# PM_Controller_v1p00.net
KiCad netlist of a schematic drawn in EAGLE
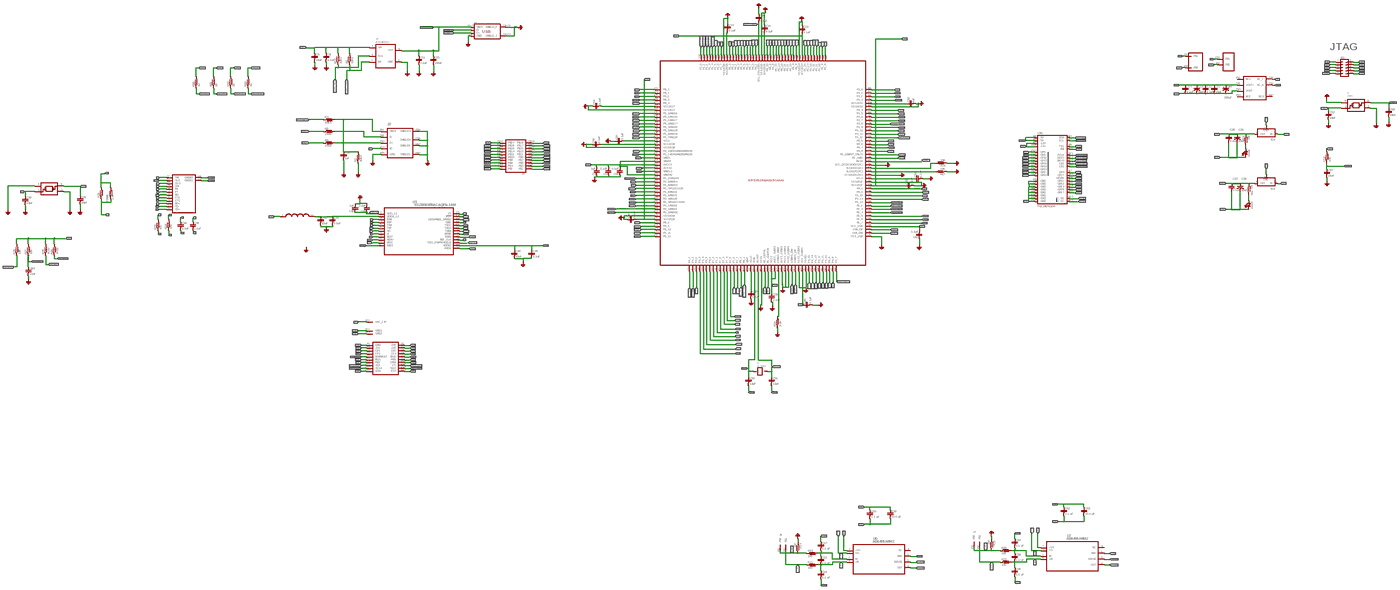
[diagram p0: schematic, sheet 1, overview]
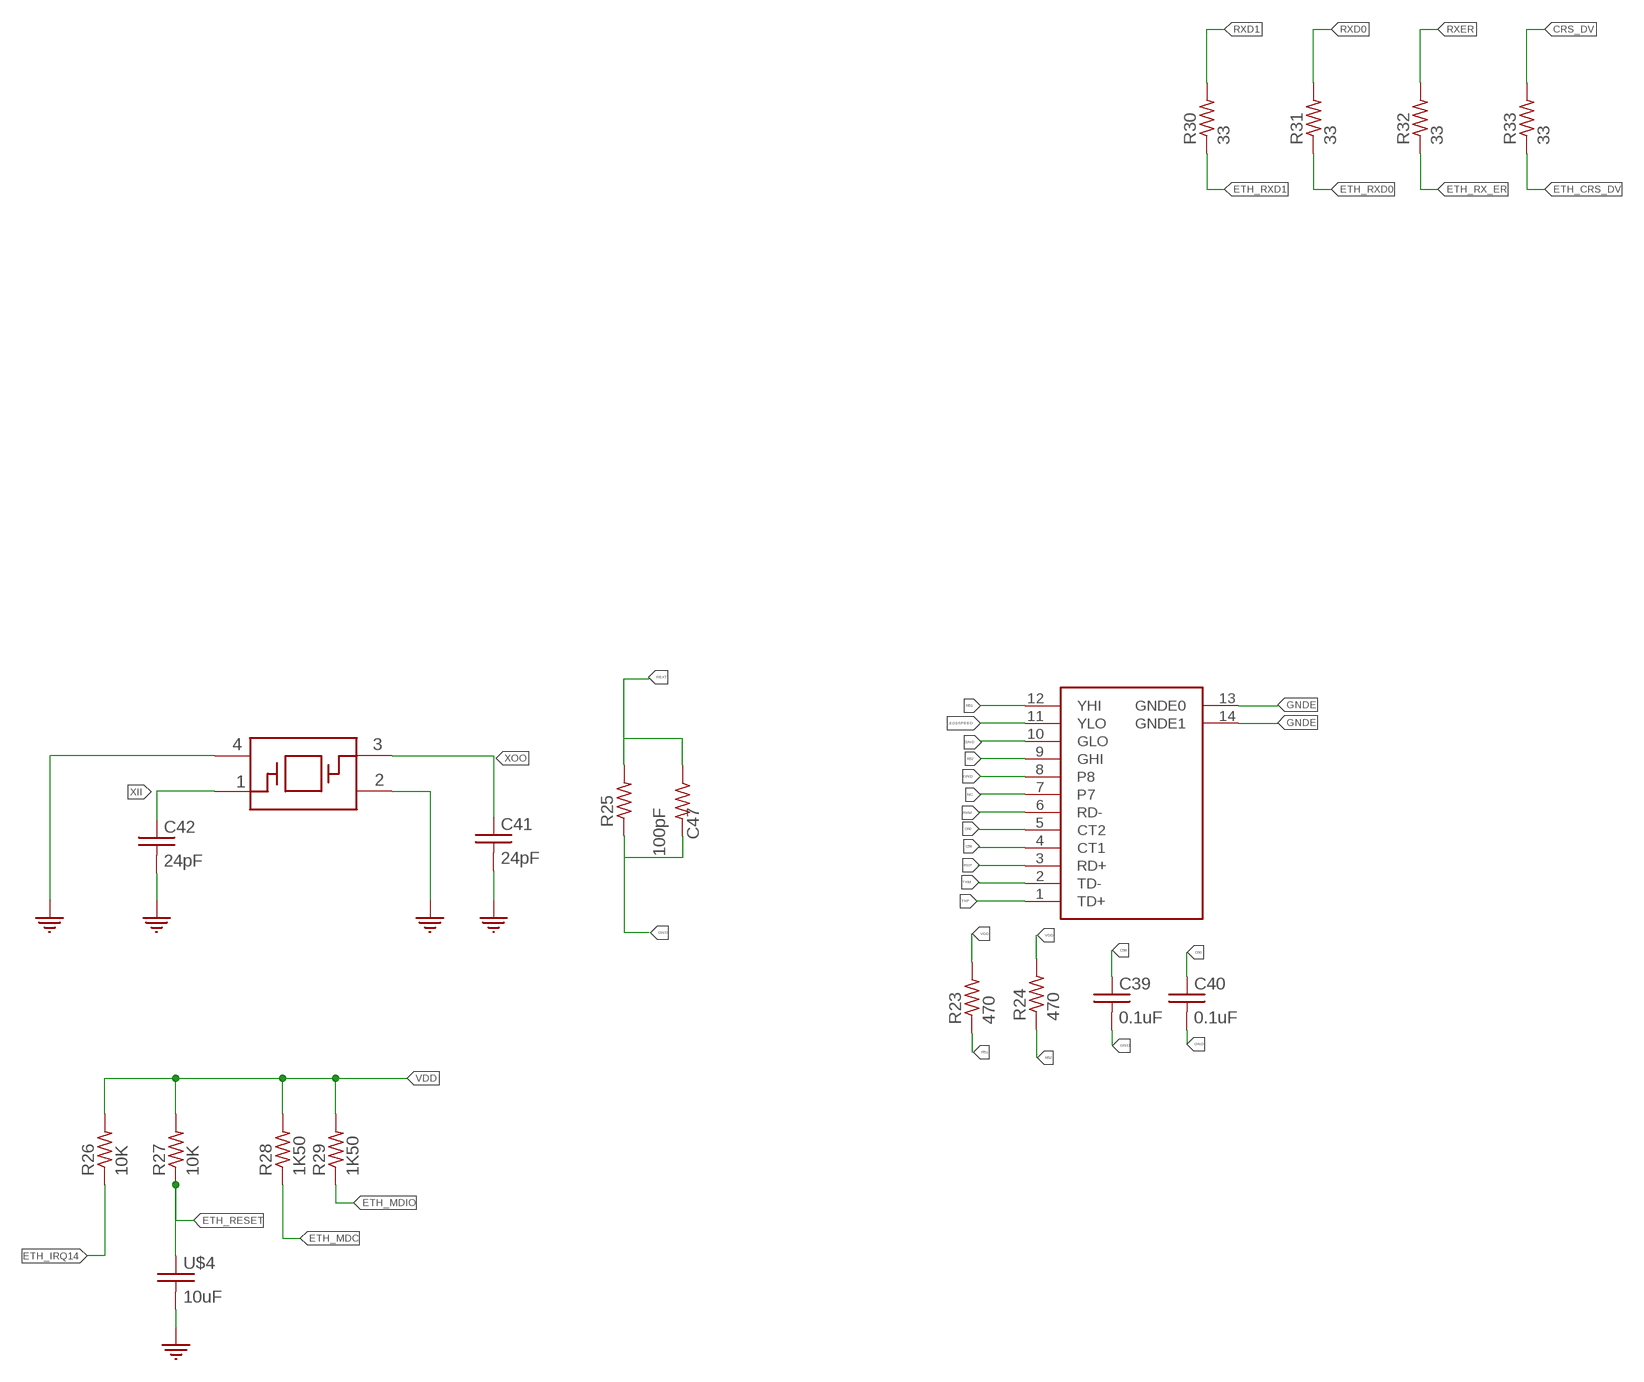
[diagram p1: schematic, sheet 1, part 1 of 6]
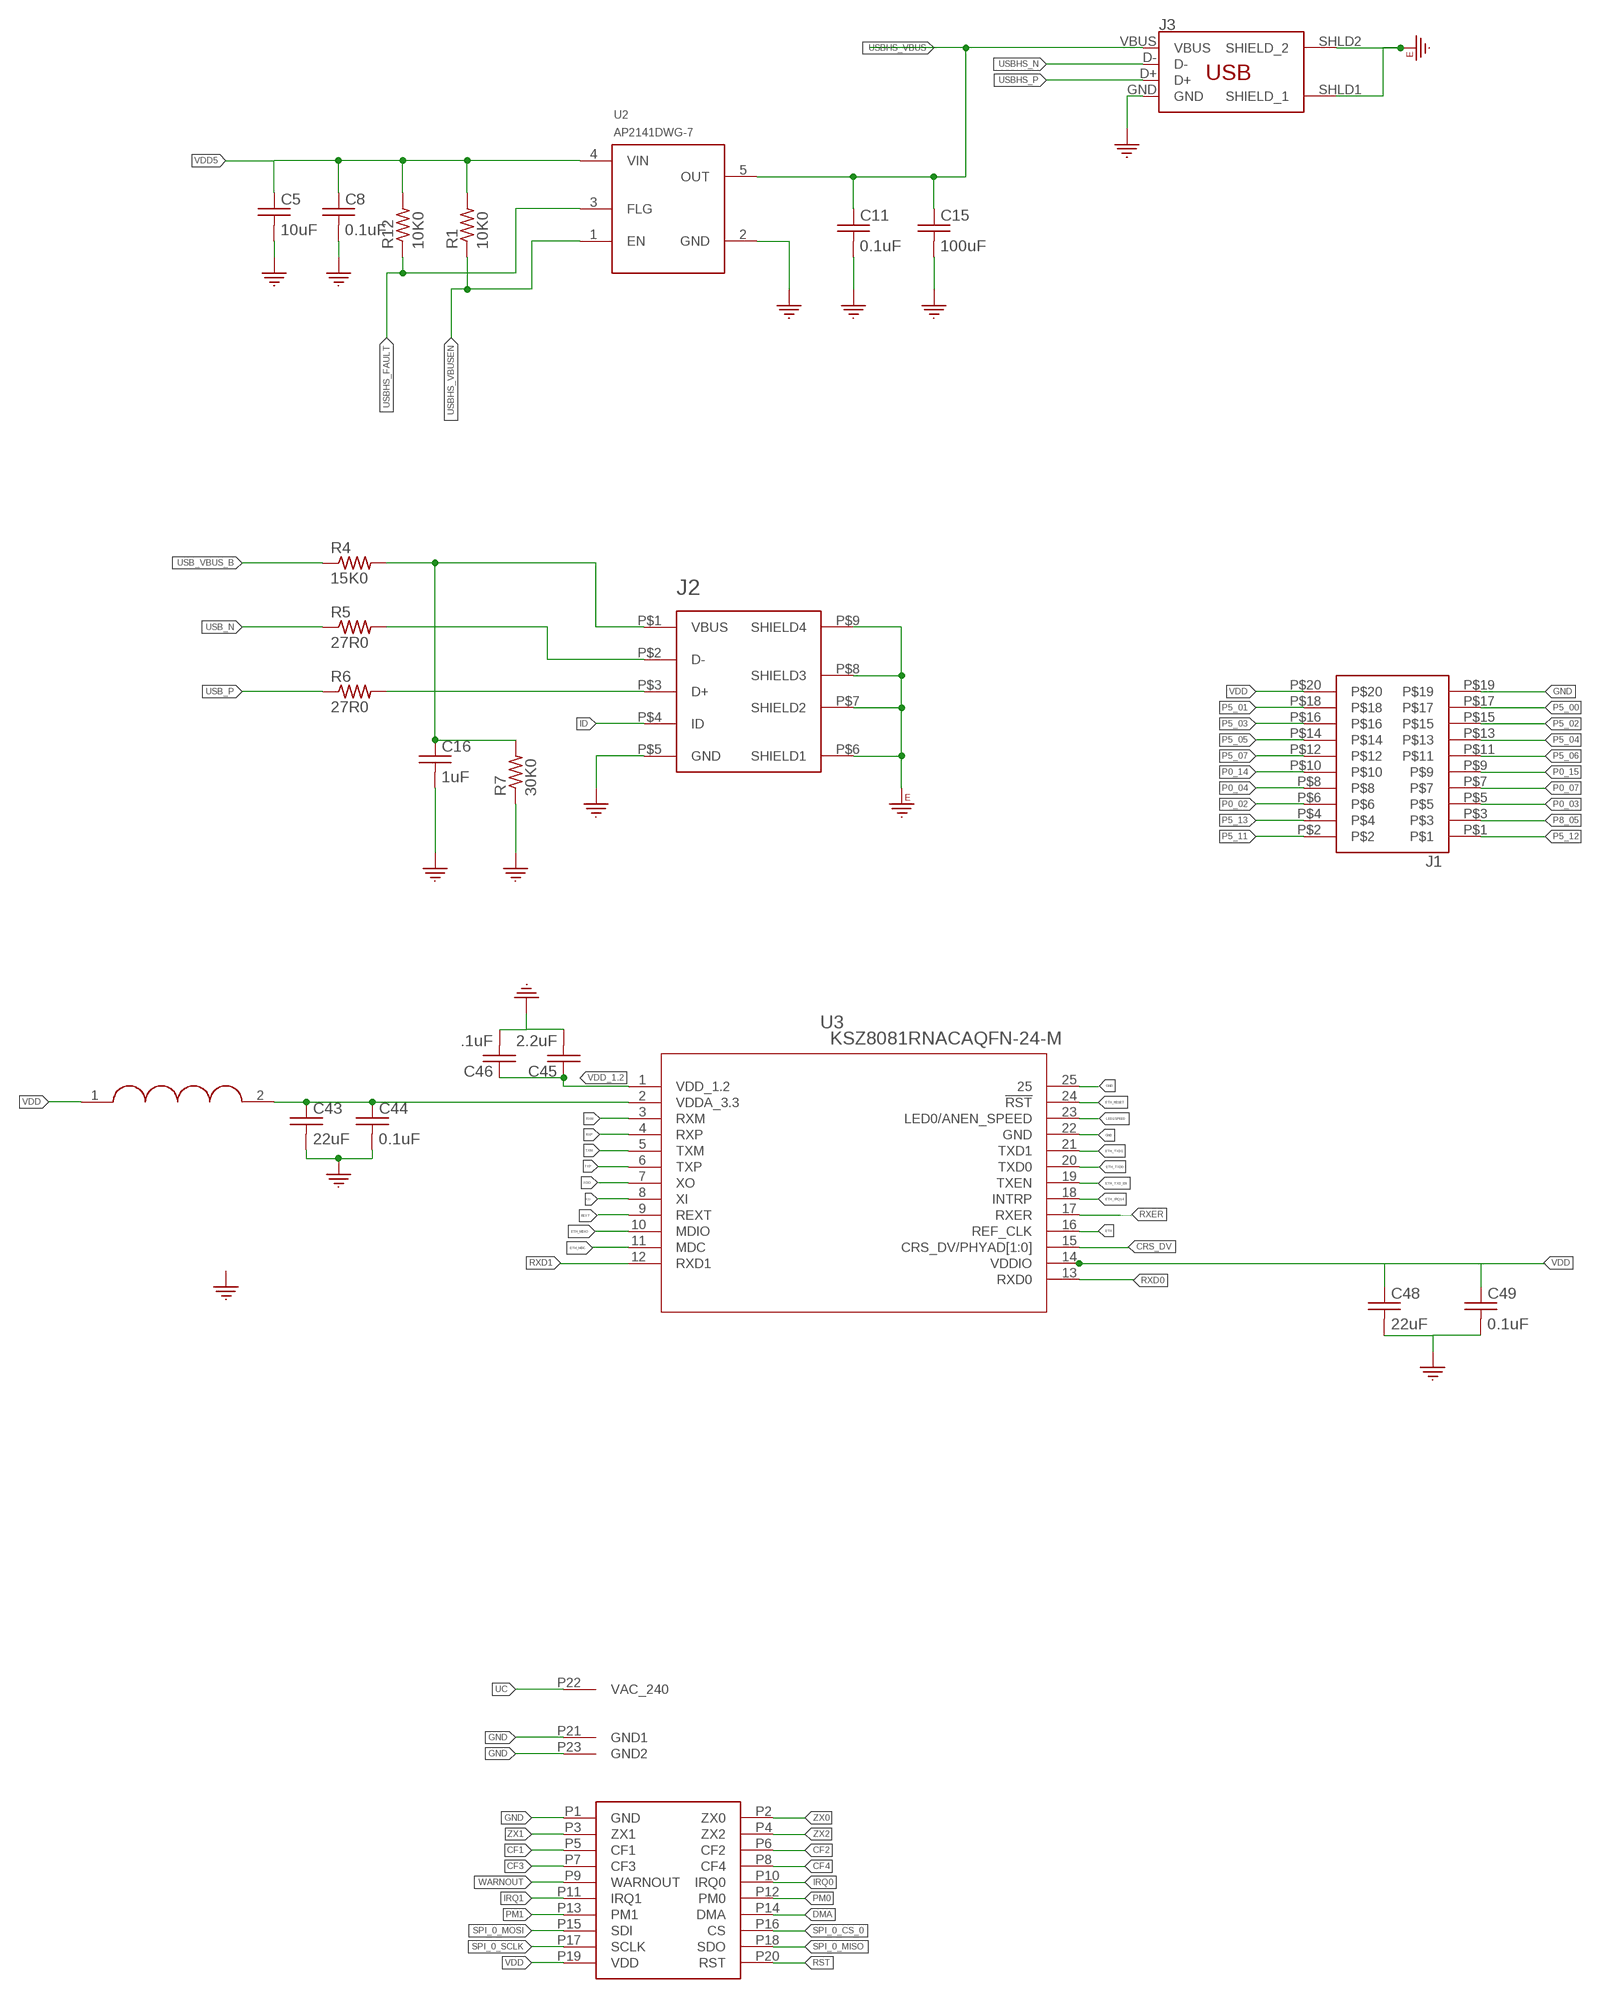
[diagram p2: schematic, sheet 1, part 2 of 6]
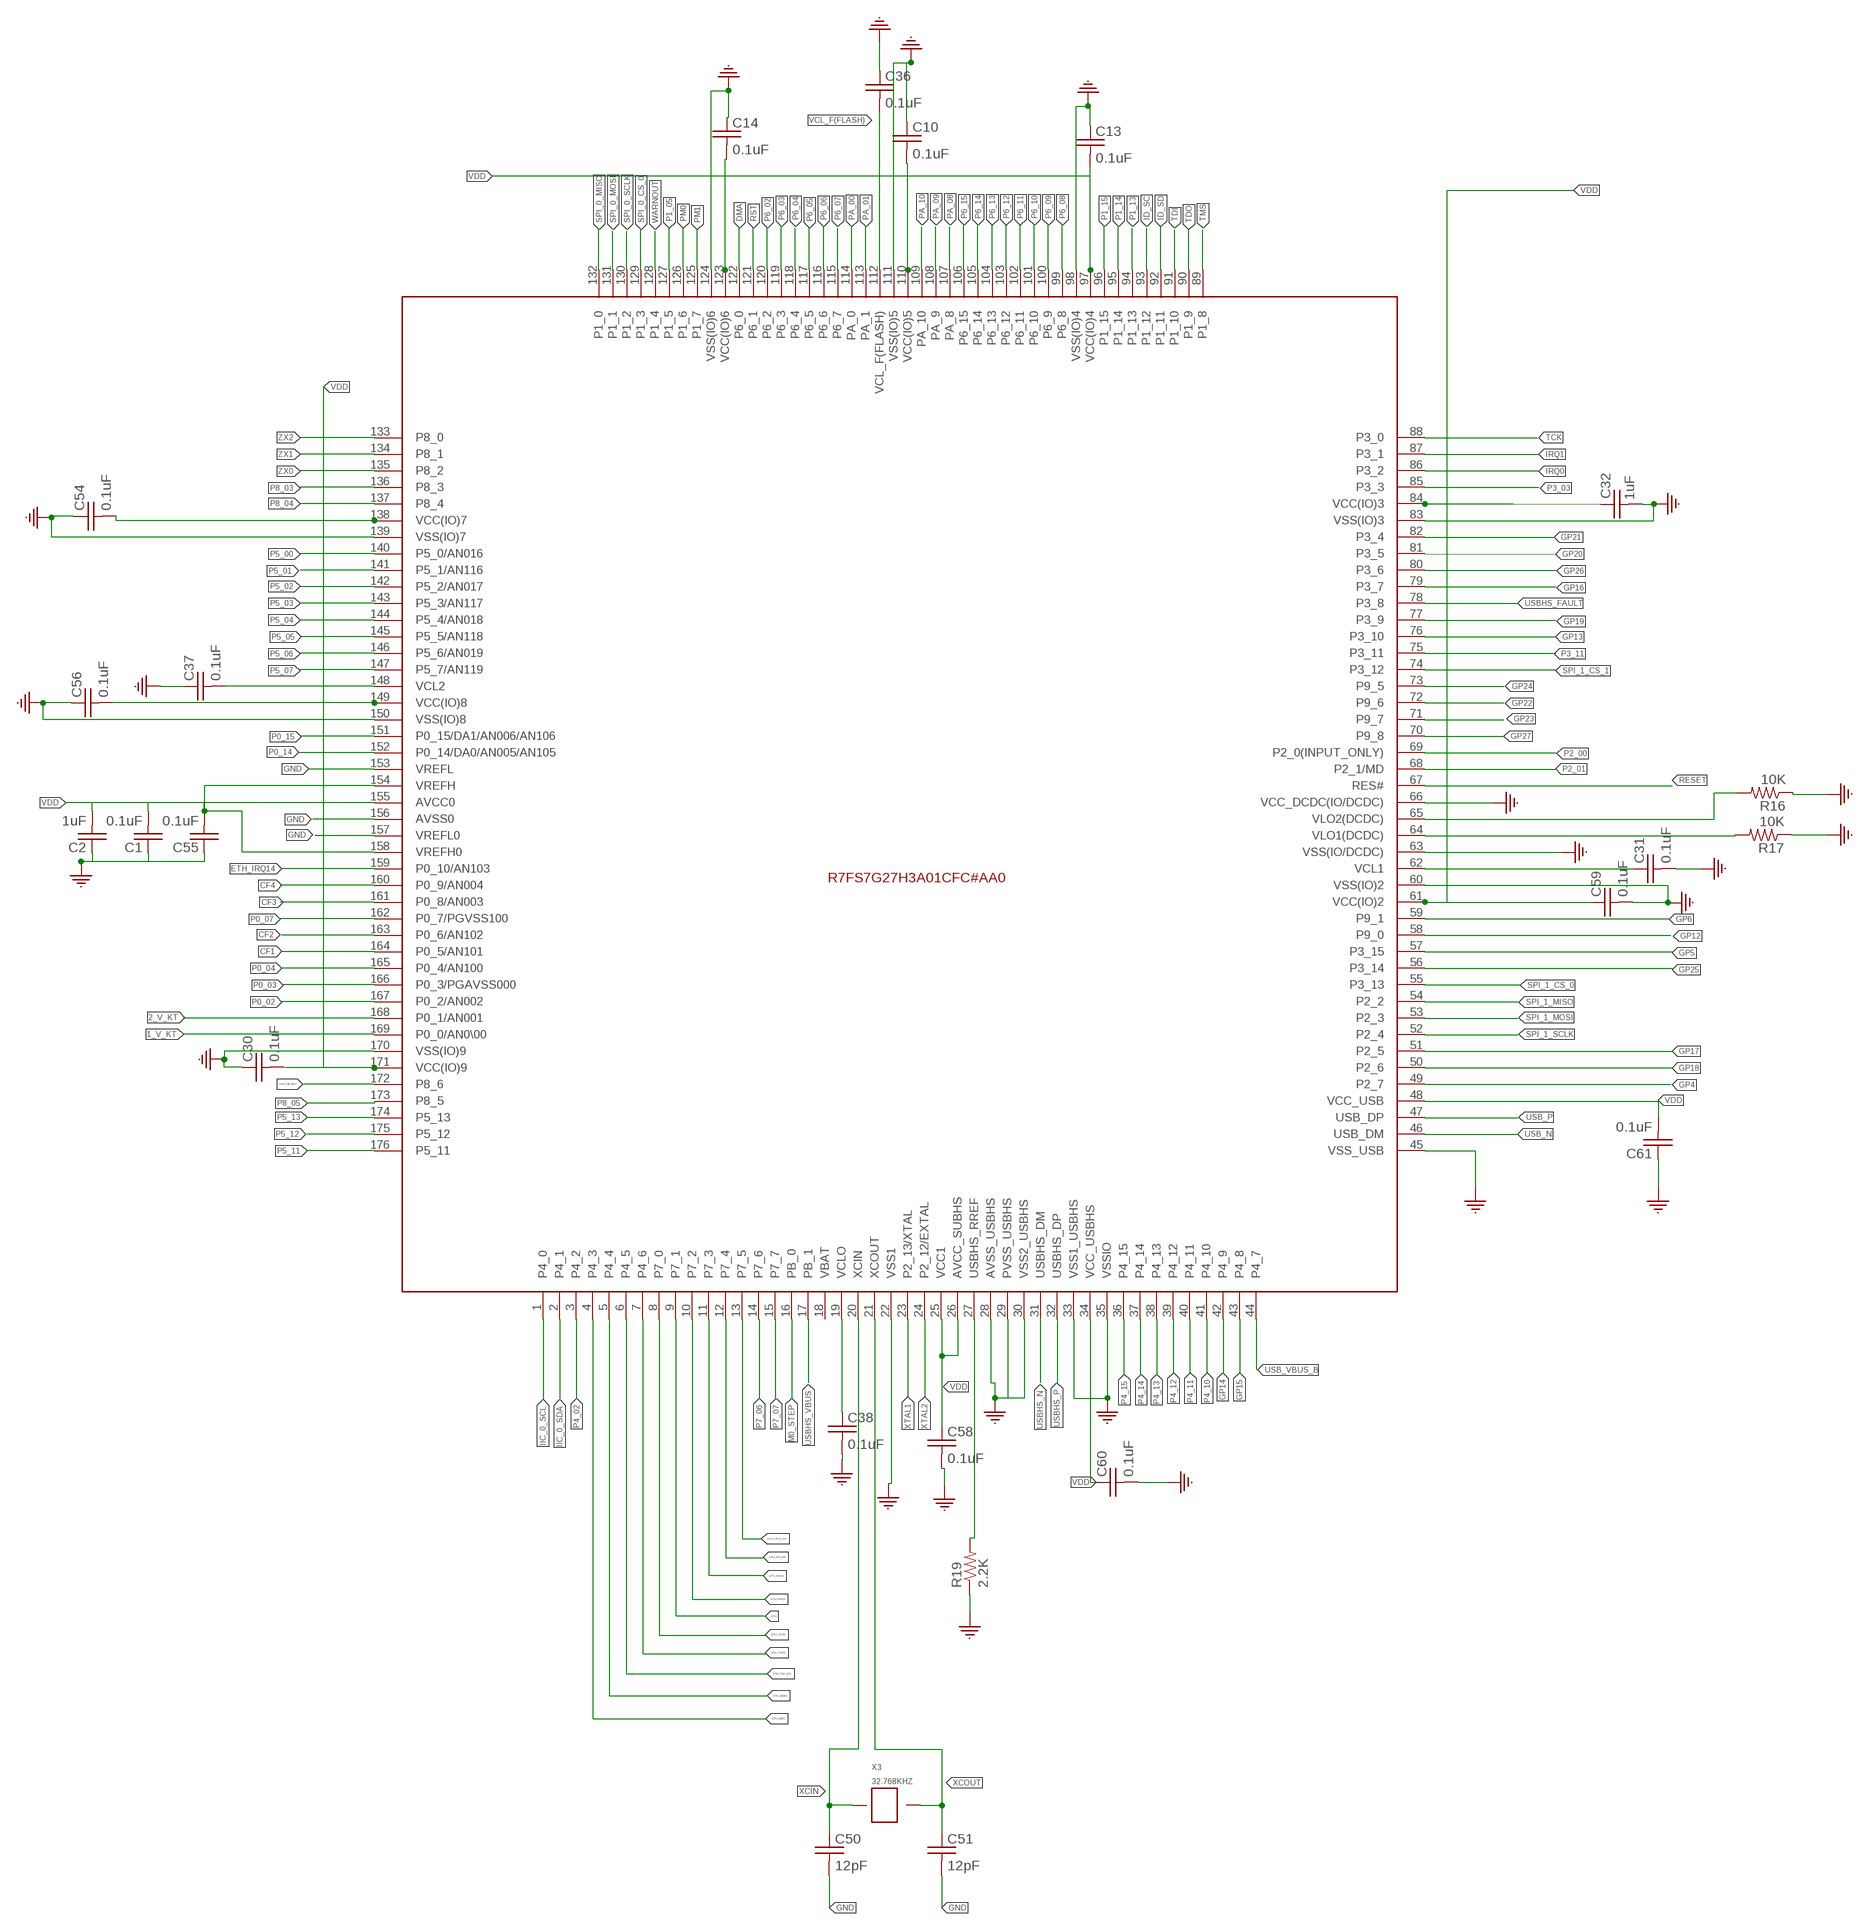
[diagram p3: schematic, sheet 1, part 3 of 6]
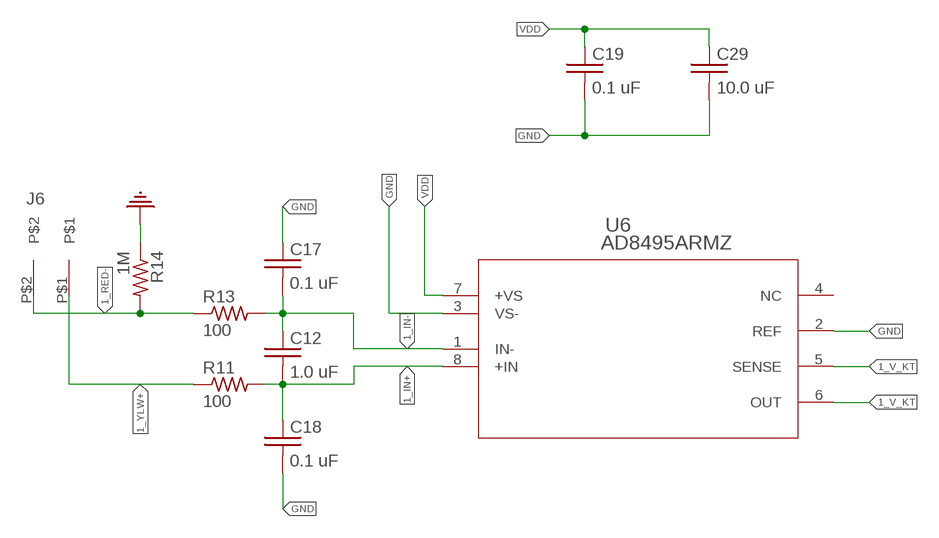
[diagram p4: schematic, sheet 1, part 4 of 6]
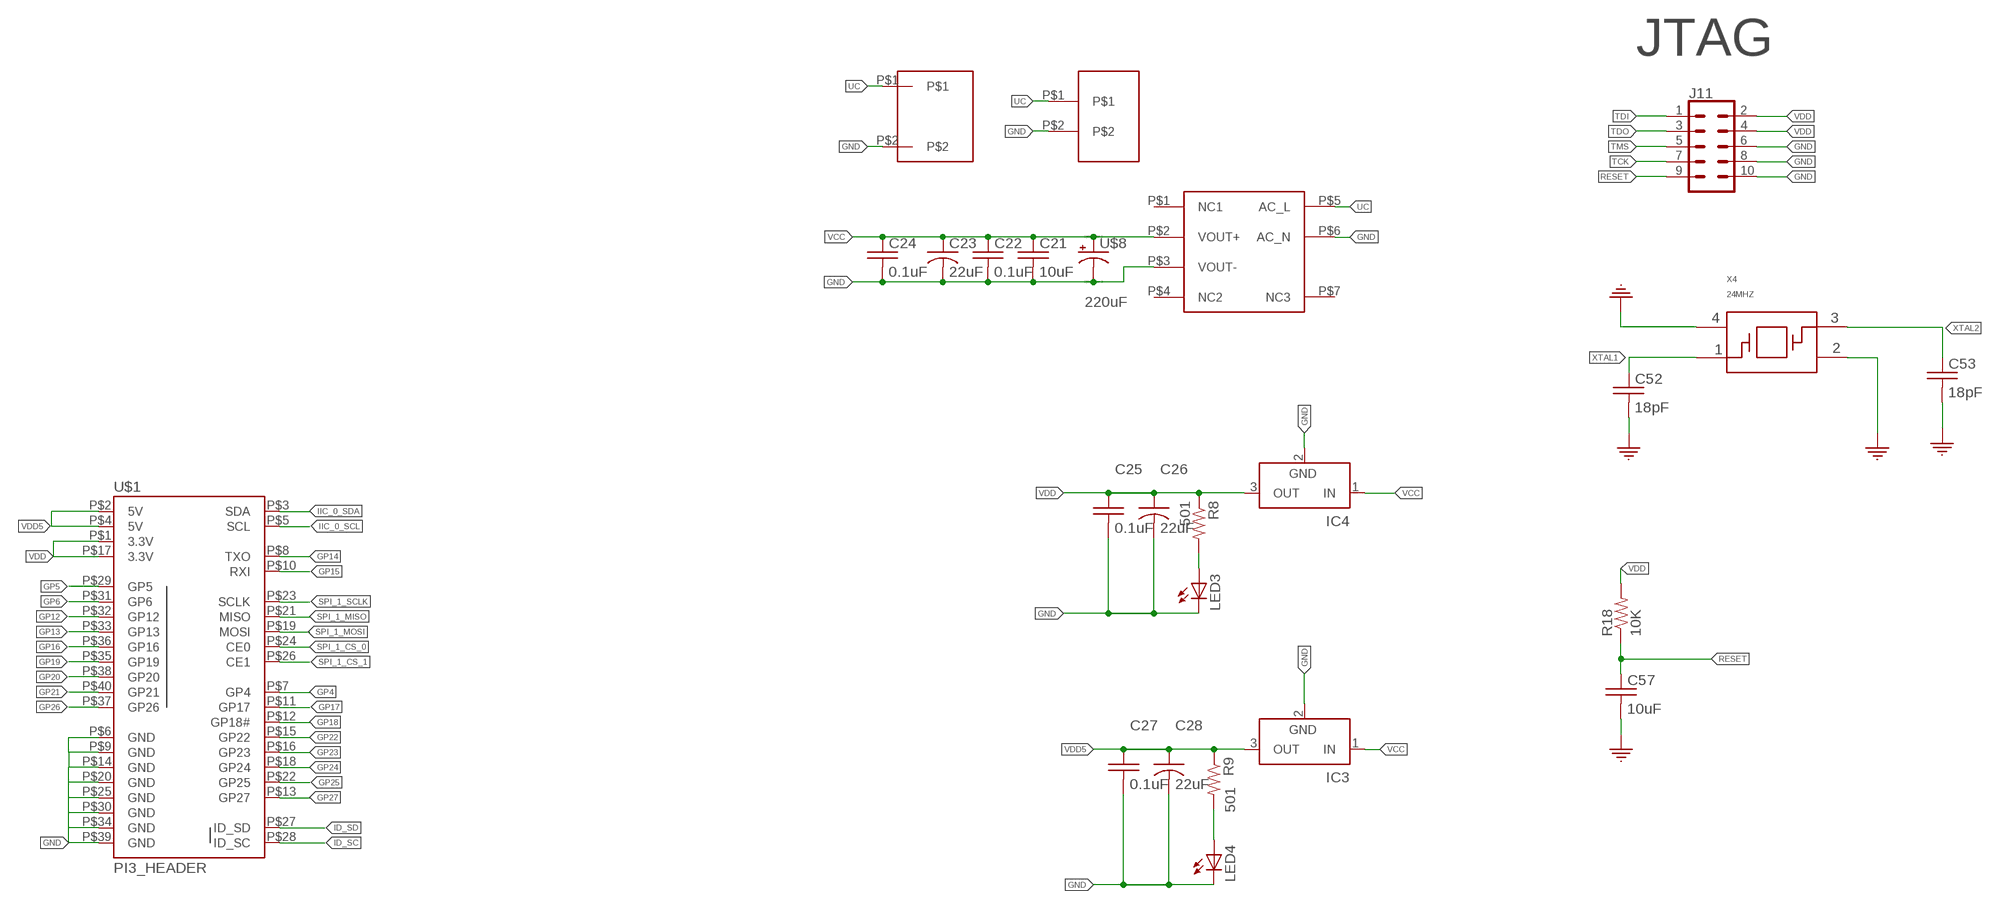
[diagram p5: schematic, sheet 1, part 5 of 6]
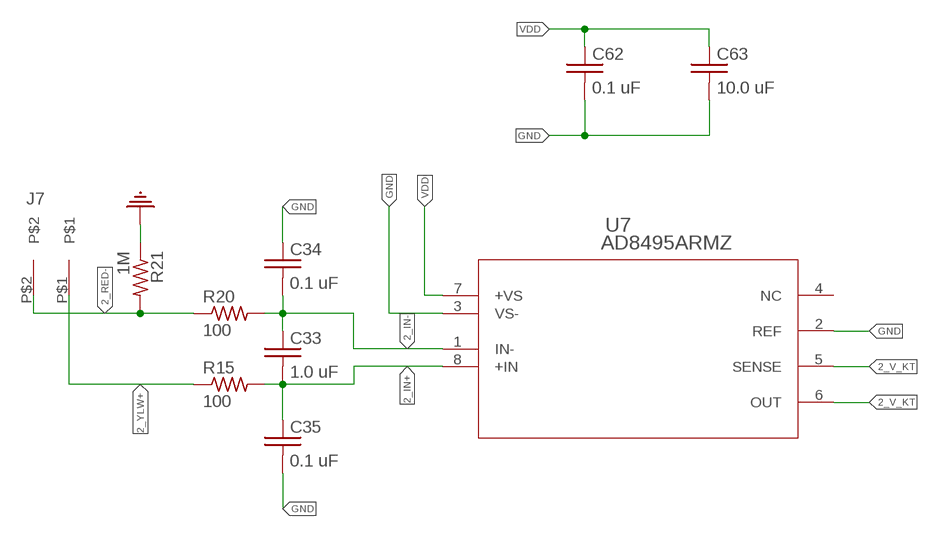
[diagram p6: schematic, sheet 1, part 6 of 6]

(export (version "E")
  (design (tool "Eeschema 10.0.6"))
  (components
    (comp (ref "C1")
      (value "0.1uF")
      (footprint "eagle-import:0402")
      (libsource (lib "eagle-import") (part "C_0402"))
    )
    (comp (ref "C2")
      (value "1uF")
      (footprint "eagle-import:0402")
      (libsource (lib "eagle-import") (part "C_0402"))
    )
    (comp (ref "C5")
      (value "10uF")
      (footprint "eagle-import:0402")
      (libsource (lib "eagle-import") (part "C_0402"))
    )
    (comp (ref "C8")
      (value "0.1uF")
      (footprint "eagle-import:0402")
      (libsource (lib "eagle-import") (part "C_0402"))
    )
    (comp (ref "C10")
      (value "0.1uF")
      (footprint "eagle-import:0402")
      (libsource (lib "eagle-import") (part "C_0402"))
    )
    (comp (ref "C11")
      (value "0.1uF")
      (footprint "eagle-import:0402")
      (libsource (lib "eagle-import") (part "C_0402"))
    )
    (comp (ref "C12")
      (value "1.0 uF")
      (footprint "eagle-import:0402")
      (libsource (lib "eagle-import") (part "C_0402"))
    )
    (comp (ref "C13")
      (value "0.1uF")
      (footprint "eagle-import:0402")
      (libsource (lib "eagle-import") (part "C_0402"))
    )
    (comp (ref "C14")
      (value "0.1uF")
      (footprint "eagle-import:0402")
      (libsource (lib "eagle-import") (part "C_0402"))
    )
    (comp (ref "C15")
      (value "100uF")
      (footprint "eagle-import:C1210")
      (libsource (lib "eagle-import") (part "C_1210"))
    )
    (comp (ref "C16")
      (value "1uF")
      (footprint "eagle-import:0402")
      (libsource (lib "eagle-import") (part "C_0402"))
    )
    (comp (ref "C17")
      (value "0.1 uF")
      (footprint "eagle-import:0402")
      (libsource (lib "eagle-import") (part "C_0402"))
    )
    (comp (ref "C18")
      (value "0.1 uF")
      (footprint "eagle-import:0402")
      (libsource (lib "eagle-import") (part "C_0402"))
    )
    (comp (ref "C19")
      (value "0.1 uF")
      (footprint "eagle-import:0402")
      (libsource (lib "eagle-import") (part "C_0402"))
    )
    (comp (ref "C20")
      (value "CAP_THIN_FILM_TDK_32922CAP")
      (footprint "eagle-import:CAP_THIN_FILM_32922")
      (libsource (lib "eagle-import") (part "CAP_THIN_FILM_TDK_32922CAP"))
    )
    (comp (ref "C21")
      (value "10uF")
      (footprint "eagle-import:0402")
      (libsource (lib "eagle-import") (part "C_0402"))
    )
    (comp (ref "C22")
      (value "0.1uF")
      (footprint "eagle-import:0402")
      (libsource (lib "eagle-import") (part "C_0402"))
    )
    (comp (ref "C23")
      (value "22uF")
      (footprint "eagle-import:C1206")
      (libsource (lib "eagle-import") (part "C-USC1206"))
    )
    (comp (ref "C24")
      (value "0.1uF")
      (footprint "eagle-import:0402")
      (libsource (lib "eagle-import") (part "C_0402"))
    )
    (comp (ref "C25")
      (value "0.1uF")
      (footprint "eagle-import:0402")
      (libsource (lib "eagle-import") (part "C_0402"))
    )
    (comp (ref "C26")
      (value "22uF")
      (footprint "eagle-import:C1206")
      (libsource (lib "eagle-import") (part "C-USC1206"))
    )
    (comp (ref "C27")
      (value "0.1uF")
      (footprint "eagle-import:0402")
      (libsource (lib "eagle-import") (part "C_0402"))
    )
    (comp (ref "C28")
      (value "22uF")
      (footprint "eagle-import:C1206")
      (libsource (lib "eagle-import") (part "C-USC1206"))
    )
    (comp (ref "C29")
      (value "10.0 uF")
      (footprint "eagle-import:0402")
      (libsource (lib "eagle-import") (part "C_0402"))
    )
    (comp (ref "C30")
      (value "0.1uF")
      (footprint "eagle-import:0402")
      (libsource (lib "eagle-import") (part "C_0402"))
    )
    (comp (ref "C31")
      (value "0.1uF")
      (footprint "eagle-import:0402")
      (libsource (lib "eagle-import") (part "C_0402"))
    )
    (comp (ref "C32")
      (value "1uF")
      (footprint "eagle-import:0402")
      (libsource (lib "eagle-import") (part "C_0402"))
    )
    (comp (ref "C33")
      (value "1.0 uF")
      (footprint "eagle-import:0402")
      (libsource (lib "eagle-import") (part "C_0402"))
    )
    (comp (ref "C34")
      (value "0.1 uF")
      (footprint "eagle-import:0402")
      (libsource (lib "eagle-import") (part "C_0402"))
    )
    (comp (ref "C35")
      (value "0.1 uF")
      (footprint "eagle-import:0402")
      (libsource (lib "eagle-import") (part "C_0402"))
    )
    (comp (ref "C36")
      (value "0.1uF")
      (footprint "eagle-import:0402")
      (libsource (lib "eagle-import") (part "C_0402"))
    )
    (comp (ref "C37")
      (value "0.1uF")
      (footprint "eagle-import:0402")
      (libsource (lib "eagle-import") (part "C_0402"))
    )
    (comp (ref "C38")
      (value "0.1uF")
      (footprint "eagle-import:0402")
      (libsource (lib "eagle-import") (part "C_0402"))
    )
    (comp (ref "C39")
      (value "0.1uF")
      (footprint "eagle-import:0402")
      (libsource (lib "eagle-import") (part "C_0402"))
    )
    (comp (ref "C40")
      (value "0.1uF")
      (footprint "eagle-import:0402")
      (libsource (lib "eagle-import") (part "C_0402"))
    )
    (comp (ref "C41")
      (value "24pF")
      (footprint "eagle-import:0402")
      (libsource (lib "eagle-import") (part "C_0402"))
    )
    (comp (ref "C42")
      (value "24pF")
      (footprint "eagle-import:0402")
      (libsource (lib "eagle-import") (part "C_0402"))
    )
    (comp (ref "C43")
      (value "22uF")
      (footprint "eagle-import:0603")
      (libsource (lib "eagle-import") (part "C_0603"))
    )
    (comp (ref "C44")
      (value "0.1uF")
      (footprint "eagle-import:0402")
      (libsource (lib "eagle-import") (part "C_0402"))
    )
    (comp (ref "C45")
      (value "2.2uF")
      (footprint "eagle-import:0402")
      (libsource (lib "eagle-import") (part "C_0402"))
    )
    (comp (ref "C46")
      (value ".1uF")
      (footprint "eagle-import:0402")
      (libsource (lib "eagle-import") (part "C_0402"))
    )
    (comp (ref "C47")
      (value "100pF")
      (footprint "eagle-import:0402")
      (libsource (lib "eagle-import") (part "R_0402"))
    )
    (comp (ref "C48")
      (value "22uF")
      (footprint "eagle-import:0603")
      (libsource (lib "eagle-import") (part "C_0603"))
    )
    (comp (ref "C49")
      (value "0.1uF")
      (footprint "eagle-import:0402")
      (libsource (lib "eagle-import") (part "C_0402"))
    )
    (comp (ref "C50")
      (value "12pF")
      (footprint "eagle-import:0402")
      (libsource (lib "eagle-import") (part "C_0402"))
    )
    (comp (ref "C51")
      (value "12pF")
      (footprint "eagle-import:0402")
      (libsource (lib "eagle-import") (part "C_0402"))
    )
    (comp (ref "C52")
      (value "18pF")
      (footprint "eagle-import:0402")
      (libsource (lib "eagle-import") (part "C_0402"))
    )
    (comp (ref "C53")
      (value "18pF")
      (footprint "eagle-import:0402")
      (libsource (lib "eagle-import") (part "C_0402"))
    )
    (comp (ref "C54")
      (value "0.1uF")
      (footprint "eagle-import:0402")
      (libsource (lib "eagle-import") (part "C_0402"))
    )
    (comp (ref "C55")
      (value "0.1uF")
      (footprint "eagle-import:0402")
      (libsource (lib "eagle-import") (part "C_0402"))
    )
    (comp (ref "C56")
      (value "0.1uF")
      (footprint "eagle-import:0402")
      (libsource (lib "eagle-import") (part "C_0402"))
    )
    (comp (ref "C57")
      (value "10uF")
      (footprint "eagle-import:0402")
      (libsource (lib "eagle-import") (part "C_0402"))
    )
    (comp (ref "C58")
      (value "0.1uF")
      (footprint "eagle-import:0402")
      (libsource (lib "eagle-import") (part "C_0402"))
    )
    (comp (ref "C59")
      (value "0.1uF")
      (footprint "eagle-import:0402")
      (libsource (lib "eagle-import") (part "C_0402"))
    )
    (comp (ref "C60")
      (value "0.1uF")
      (footprint "eagle-import:0402")
      (libsource (lib "eagle-import") (part "C_0402"))
    )
    (comp (ref "C61")
      (value "0.1uF")
      (footprint "eagle-import:0402")
      (libsource (lib "eagle-import") (part "C_0402"))
    )
    (comp (ref "C62")
      (value "0.1 uF")
      (footprint "eagle-import:0402")
      (libsource (lib "eagle-import") (part "C_0402"))
    )
    (comp (ref "C63")
      (value "10.0 uF")
      (footprint "eagle-import:0402")
      (libsource (lib "eagle-import") (part "C_0402"))
    )
    (comp (ref "FB2/2")
      (value "FB_0805_120_OHM")
      (footprint "eagle-import:0805")
      (libsource (lib "eagle-import") (part "FB_0805_120_OHM"))
    )
    (comp (ref "IC3")
      (value "LT1129CST5")
      (footprint "eagle-import:SOT223")
      (fields (field (name "MPN") "LT1129CST-5#PBF"))
      (libsource (lib "eagle-import") (part "LT1129CST5"))
    )
    (comp (ref "IC4")
      (value "LT1129CST3")
      (footprint "eagle-import:SOT223")
      (fields (field (name "MPN") "LT1129CST-5#PBF"))
      (libsource (lib "eagle-import") (part "LT1129CST3"))
    )
    (comp (ref "J1")
      (value "2_X_10_HEADER_GENERIC")
      (footprint "eagle-import:2_X_10_.1_INCH")
      (libsource (lib "eagle-import") (part "2_X_10_HEADER_GENERIC"))
    )
    (comp (ref "J2")
      (value "USB_MICRO-B")
      (footprint "eagle-import:USB_MICRO-B")
      (libsource (lib "eagle-import") (part "USB_MICRO-B"))
    )
    (comp (ref "J3")
      (value "USB_A")
      (footprint "eagle-import:USB_A_SMT")
      (libsource (lib "eagle-import") (part "USB_A"))
    )
    (comp (ref "J4")
      (value "RJ45_WITH_ELEC")
      (footprint "eagle-import:RJ45_TH_ELEC")
      (libsource (lib "eagle-import") (part "RJ45_WITH_ELEC"))
    )
    (comp (ref "J6")
      (value "3.81MM_1_X_2_RT_ANGLE_PLUG_HEADER")
      (footprint "eagle-import:2_3.81MM_PITCH")
      (libsource (lib "eagle-import") (part "3.81MM_1_X_2_RT_ANGLE_PLUG_HEADER"))
    )
    (comp (ref "J7")
      (value "3.81MM_1_X_2_RT_ANGLE_PLUG_HEADER")
      (footprint "eagle-import:2_3.81MM_PITCH")
      (libsource (lib "eagle-import") (part "3.81MM_1_X_2_RT_ANGLE_PLUG_HEADER"))
    )
    (comp (ref "J11")
      (value "CONN_05X2PTH")
      (footprint "eagle-import:2X5")
      (libsource (lib "eagle-import") (part "CONN_05X2PTH"))
    )
    (comp (ref "LED3")
      (value "LED_0805_GREEN")
      (footprint "eagle-import:LED_0805_GREEN")
      (libsource (lib "eagle-import") (part "LED_0805_GREEN"))
    )
    (comp (ref "LED4")
      (value "LED_0805_GREEN")
      (footprint "eagle-import:LED_0805_GREEN")
      (libsource (lib "eagle-import") (part "LED_0805_GREEN"))
    )
    (comp (ref "R1")
      (value "10K0")
      (footprint "eagle-import:0402")
      (libsource (lib "eagle-import") (part "R_0402"))
    )
    (comp (ref "R4")
      (value "15K0")
      (footprint "eagle-import:0402")
      (libsource (lib "eagle-import") (part "R_0402"))
    )
    (comp (ref "R5")
      (value "27R0")
      (footprint "eagle-import:0402")
      (libsource (lib "eagle-import") (part "R_0402"))
    )
    (comp (ref "R6")
      (value "27R0")
      (footprint "eagle-import:0402")
      (libsource (lib "eagle-import") (part "R_0402"))
    )
    (comp (ref "R7")
      (value "30K0")
      (footprint "eagle-import:0402")
      (libsource (lib "eagle-import") (part "R_0402"))
    )
    (comp (ref "R8")
      (value "501")
      (footprint "eagle-import:0402")
      (libsource (lib "eagle-import") (part "R_0402"))
    )
    (comp (ref "R9")
      (value "501")
      (footprint "eagle-import:0402")
      (libsource (lib "eagle-import") (part "R_0402"))
    )
    (comp (ref "R11")
      (value "100")
      (footprint "eagle-import:0402")
      (libsource (lib "eagle-import") (part "R_0402"))
    )
    (comp (ref "R12")
      (value "10K0")
      (footprint "eagle-import:0402")
      (libsource (lib "eagle-import") (part "R_0402"))
    )
    (comp (ref "R13")
      (value "100")
      (footprint "eagle-import:0402")
      (libsource (lib "eagle-import") (part "R_0402"))
    )
    (comp (ref "R14")
      (value "1M")
      (footprint "eagle-import:0402")
      (libsource (lib "eagle-import") (part "R_0402"))
    )
    (comp (ref "R15")
      (value "100")
      (footprint "eagle-import:0402")
      (libsource (lib "eagle-import") (part "R_0402"))
    )
    (comp (ref "R16")
      (value "10K")
      (footprint "eagle-import:0402")
      (libsource (lib "eagle-import") (part "R_0402"))
    )
    (comp (ref "R17")
      (value "10K")
      (footprint "eagle-import:0402")
      (libsource (lib "eagle-import") (part "R_0402"))
    )
    (comp (ref "R18")
      (value "10K")
      (footprint "eagle-import:0402")
      (libsource (lib "eagle-import") (part "R_0402"))
    )
    (comp (ref "R19")
      (value "2.2K")
      (footprint "eagle-import:0402")
      (libsource (lib "eagle-import") (part "R_0402"))
    )
    (comp (ref "R20")
      (value "100")
      (footprint "eagle-import:0402")
      (libsource (lib "eagle-import") (part "R_0402"))
    )
    (comp (ref "R21")
      (value "1M")
      (footprint "eagle-import:0402")
      (libsource (lib "eagle-import") (part "R_0402"))
    )
    (comp (ref "R23")
      (value "470")
      (footprint "eagle-import:0402")
      (libsource (lib "eagle-import") (part "R_0402"))
    )
    (comp (ref "R24")
      (value "470")
      (footprint "eagle-import:0402")
      (libsource (lib "eagle-import") (part "R_0402"))
    )
    (comp (ref "R25")
      (value "6k49")
      (footprint "eagle-import:0402")
      (libsource (lib "eagle-import") (part "R_0402"))
    )
    (comp (ref "R26")
      (value "10K")
      (footprint "eagle-import:0402")
      (libsource (lib "eagle-import") (part "R_0402"))
    )
    (comp (ref "R27")
      (value "10K")
      (footprint "eagle-import:0402")
      (libsource (lib "eagle-import") (part "R_0402"))
    )
    (comp (ref "R28")
      (value "1K50")
      (footprint "eagle-import:0402")
      (libsource (lib "eagle-import") (part "R_0402"))
    )
    (comp (ref "R29")
      (value "1K50")
      (footprint "eagle-import:0402")
      (libsource (lib "eagle-import") (part "R_0402"))
    )
    (comp (ref "R30")
      (value "33")
      (footprint "eagle-import:0402")
      (libsource (lib "eagle-import") (part "R_0402"))
    )
    (comp (ref "R31")
      (value "33")
      (footprint "eagle-import:0402")
      (libsource (lib "eagle-import") (part "R_0402"))
    )
    (comp (ref "R32")
      (value "33")
      (footprint "eagle-import:0402")
      (libsource (lib "eagle-import") (part "R_0402"))
    )
    (comp (ref "R33")
      (value "33")
      (footprint "eagle-import:0402")
      (libsource (lib "eagle-import") (part "R_0402"))
    )
    (comp (ref "U$1")
      (value "PI3_HEADER")
      (footprint "eagle-import:HEADER_2_X_20_.1_INCH")
      (libsource (lib "eagle-import") (part "PI3_HEADER"))
    )
    (comp (ref "U$2")
      (value "METER_BASE")
      (footprint "eagle-import:METER_BASE")
      (libsource (lib "eagle-import") (part "METER_BASE"))
    )
    (comp (ref "U$3")
      (value "XTAL_25_MHZ")
      (footprint "eagle-import:SMD_3225")
      (libsource (lib "eagle-import") (part "XTAL_25_MHZ"))
    )
    (comp (ref "U$4")
      (value "10uF")
      (footprint "eagle-import:0402")
      (libsource (lib "eagle-import") (part "C_0402"))
    )
    (comp (ref "U$7")
      (value "VAR_10MM_VDRUS10")
      (footprint "eagle-import:VAR_10MM_VDRUS10")
      (libsource (lib "eagle-import") (part "VAR_10MM_VDRUS10"))
    )
    (comp (ref "U$8")
      (value "220uF")
      (footprint "eagle-import:C_AL_ELECTROLYTIC_SMD_220UF")
      (libsource (lib "eagle-import") (part "C_AL_ELECTROLYTIC_SMD_220UF"))
    )
    (comp (ref "U2")
      (value "AP2141DWG-5")
      (footprint "eagle-import:SOT-23-5")
      (libsource (lib "eagle-import") (part "AP2141DWG-5"))
    )
    (comp (ref "U3")
      (value "KSZ8081RNACAQFN-24-M")
      (footprint "eagle-import:QFN-24-M")
      (fields (field (name "MANUFACTURER_PART_NUMBER") "KSZ8081RNACA"))
      (libsource (lib "eagle-import") (part "KSZ8081RNACAQFN-24-M"))
    )
    (comp (ref "U4")
      (value "S7G2_X_176")
      (footprint "eagle-import:LQFP176_24X24")
      (libsource (lib "eagle-import") (part "S7G2_X_176"))
    )
    (comp (ref "U5")
      (value "TMLM_04109")
      (footprint "eagle-import:TMLM04")
      (libsource (lib "eagle-import") (part "TMLM_04109"))
    )
    (comp (ref "U6")
      (value "AD8495ARMZ")
      (footprint "eagle-import:RM_8_ADI")
      (libsource (lib "eagle-import") (part "AD8495ARMZ"))
    )
    (comp (ref "U7")
      (value "AD8495ARMZ")
      (footprint "eagle-import:RM_8_ADI")
      (libsource (lib "eagle-import") (part "AD8495ARMZ"))
    )
    (comp (ref "X3")
      (value "32.768KHZ")
      (footprint "eagle-import:SMD_X_2_PADS")
      (libsource (lib "eagle-import") (part "XTAL_32.768KHZ"))
    )
    (comp (ref "X4")
      (value "24MHZ")
      (footprint "eagle-import:SMD_3225")
      (libsource (lib "eagle-import") (part "XTAL_24_MHZ"))
    )
  )
  (nets
    (net (code "1") (name "1_IN+") (class "Default")
      (node (ref "C12") (pin "P$2") (pinfunction "2_P$2") (pintype "passive"))
      (node (ref "C18") (pin "P$1") (pinfunction "1_P$1") (pintype "passive"))
      (node (ref "R11") (pin "P$2") (pinfunction "2_P$2") (pintype "passive"))
      (node (ref "U6") (pin "8") (pinfunction "+IN_8") (pintype "input"))
    )
    (net (code "2") (name "1_IN-") (class "Default")
      (node (ref "C12") (pin "P$1") (pinfunction "1_P$1") (pintype "passive"))
      (node (ref "C17") (pin "P$2") (pinfunction "2_P$2") (pintype "passive"))
      (node (ref "R13") (pin "P$2") (pinfunction "2_P$2") (pintype "passive"))
      (node (ref "U6") (pin "1") (pinfunction "IN-_1") (pintype "input"))
    )
    (net (code "3") (name "1_RED-") (class "Default")
      (node (ref "J6") (pin "P$2") (pinfunction "P$2_P$2") (pintype "bidirectional"))
      (node (ref "R13") (pin "P$1") (pinfunction "1_P$1") (pintype "passive"))
      (node (ref "R14") (pin "P$2") (pinfunction "2_P$2") (pintype "passive"))
    )
    (net (code "4") (name "1_V_KT") (class "Default")
      (node (ref "U4") (pin "169") (pinfunction "P0_0/AN0\\00_169") (pintype "bidirectional"))
      (node (ref "U6") (pin "5") (pinfunction "SENSE_5") (pintype "passive"))
      (node (ref "U6") (pin "6") (pinfunction "OUT_6") (pintype "output"))
    )
    (net (code "5") (name "1_YLW+") (class "Default")
      (node (ref "J6") (pin "P$1") (pinfunction "P$1_P$1") (pintype "bidirectional"))
      (node (ref "R11") (pin "P$1") (pinfunction "1_P$1") (pintype "passive"))
    )
    (net (code "6") (name "2_IN+") (class "Default")
      (node (ref "C33") (pin "P$2") (pinfunction "2_P$2") (pintype "passive"))
      (node (ref "C35") (pin "P$1") (pinfunction "1_P$1") (pintype "passive"))
      (node (ref "R15") (pin "P$2") (pinfunction "2_P$2") (pintype "passive"))
      (node (ref "U7") (pin "8") (pinfunction "+IN_8") (pintype "input"))
    )
    (net (code "7") (name "2_IN-") (class "Default")
      (node (ref "C33") (pin "P$1") (pinfunction "1_P$1") (pintype "passive"))
      (node (ref "C34") (pin "P$2") (pinfunction "2_P$2") (pintype "passive"))
      (node (ref "R20") (pin "P$2") (pinfunction "2_P$2") (pintype "passive"))
      (node (ref "U7") (pin "1") (pinfunction "IN-_1") (pintype "input"))
    )
    (net (code "8") (name "2_RED-") (class "Default")
      (node (ref "J7") (pin "P$2") (pinfunction "P$2_P$2") (pintype "bidirectional"))
      (node (ref "R20") (pin "P$1") (pinfunction "1_P$1") (pintype "passive"))
      (node (ref "R21") (pin "P$2") (pinfunction "2_P$2") (pintype "passive"))
    )
    (net (code "9") (name "2_V_KT") (class "Default")
      (node (ref "U4") (pin "168") (pinfunction "P0_1/AN001_168") (pintype "bidirectional"))
      (node (ref "U7") (pin "5") (pinfunction "SENSE_5") (pintype "passive"))
      (node (ref "U7") (pin "6") (pinfunction "OUT_6") (pintype "output"))
    )
    (net (code "10") (name "2_YLW+") (class "Default")
      (node (ref "J7") (pin "P$1") (pinfunction "P$1_P$1") (pintype "bidirectional"))
      (node (ref "R15") (pin "P$1") (pinfunction "1_P$1") (pintype "passive"))
    )
    (net (code "11") (name "C58") (class "Default")
      (node (ref "C39") (pin "P$1") (pinfunction "1_P$1") (pintype "passive"))
      (node (ref "J4") (pin "4") (pinfunction "CT1_4") (pintype "bidirectional"))
    )
    (net (code "12") (name "C60") (class "Default")
      (node (ref "C40") (pin "P$1") (pinfunction "1_P$1") (pintype "passive"))
      (node (ref "J4") (pin "5") (pinfunction "CT2_5") (pintype "bidirectional"))
    )
    (net (code "13") (name "CF1") (class "Default")
      (node (ref "U$2") (pin "P5") (pinfunction "CF1_P5") (pintype "bidirectional"))
      (node (ref "U4") (pin "164") (pinfunction "P0_5/AN101_164") (pintype "bidirectional"))
    )
    (net (code "14") (name "CF2") (class "Default")
      (node (ref "U$2") (pin "P6") (pinfunction "CF2_P6") (pintype "bidirectional"))
      (node (ref "U4") (pin "163") (pinfunction "P0_6/AN102_163") (pintype "bidirectional"))
    )
    (net (code "15") (name "CF3") (class "Default")
      (node (ref "U$2") (pin "P7") (pinfunction "CF3_P7") (pintype "bidirectional"))
      (node (ref "U4") (pin "161") (pinfunction "P0_8/AN003_161") (pintype "bidirectional"))
    )
    (net (code "16") (name "CF4") (class "Default")
      (node (ref "U$2") (pin "P8") (pinfunction "CF4_P8") (pintype "bidirectional"))
      (node (ref "U4") (pin "160") (pinfunction "P0_9/AN004_160") (pintype "bidirectional"))
    )
    (net (code "17") (name "CRS_DV") (class "Default")
      (node (ref "R33") (pin "P$2") (pinfunction "2_P$2") (pintype "passive"))
      (node (ref "U3") (pin "15") (pinfunction "CRS_DV/PHYAD[1:0]_15") (pintype "bidirectional"))
    )
    (net (code "18") (name "DMA") (class "Default")
      (node (ref "U$2") (pin "P14") (pinfunction "DMA_P14") (pintype "bidirectional"))
      (node (ref "U4") (pin "122") (pinfunction "P6_0_122") (pintype "bidirectional"))
    )
    (net (code "19") (name "ETH") (class "Default")
      (node (ref "U3") (pin "16") (pinfunction "REF_CLK_16") (pintype "bidirectional"))
      (node (ref "U4") (pin "9") (pinfunction "P7_1_9") (pintype "bidirectional"))
    )
    (net (code "20") (name "ETH_CRS_DV") (class "Default")
      (node (ref "R33") (pin "P$1") (pinfunction "1_P$1") (pintype "passive"))
      (node (ref "U4") (pin "13") (pinfunction "P7_5_13") (pintype "bidirectional"))
    )
    (net (code "21") (name "ETH_IRQ14") (class "Default")
      (node (ref "R26") (pin "P$1") (pinfunction "1_P$1") (pintype "passive"))
      (node (ref "U3") (pin "18") (pinfunction "INTRP_18") (pintype "bidirectional"))
      (node (ref "U4") (pin "159") (pinfunction "P0_10/AN103_159") (pintype "bidirectional"))
    )
    (net (code "22") (name "ETH_MDC") (class "Default")
      (node (ref "R28") (pin "P$1") (pinfunction "1_P$1") (pintype "passive"))
      (node (ref "U3") (pin "11") (pinfunction "MDC_11") (pintype "input"))
      (node (ref "U4") (pin "4") (pinfunction "P4_3_4") (pintype "bidirectional"))
    )
    (net (code "23") (name "ETH_MDIO") (class "Default")
      (node (ref "R29") (pin "P$1") (pinfunction "1_P$1") (pintype "passive"))
      (node (ref "U3") (pin "10") (pinfunction "MDIO_10") (pintype "bidirectional"))
      (node (ref "U4") (pin "5") (pinfunction "P4_4_5") (pintype "bidirectional"))
    )
    (net (code "24") (name "ETH_RESET") (class "Default")
      (node (ref "R27") (pin "P$1") (pinfunction "1_P$1") (pintype "passive"))
      (node (ref "U$4") (pin "P$1") (pinfunction "1_P$1") (pintype "passive"))
      (node (ref "U3") (pin "24") (pinfunction "~{RST}_24") (pintype "input"))
      (node (ref "U4") (pin "172") (pinfunction "P8_6_172") (pintype "bidirectional"))
    )
    (net (code "25") (name "ETH_RXD0") (class "Default")
      (node (ref "R31") (pin "P$1") (pinfunction "1_P$1") (pintype "passive"))
      (node (ref "U4") (pin "10") (pinfunction "P7_2_10") (pintype "bidirectional"))
    )
    (net (code "26") (name "ETH_RXD1") (class "Default")
      (node (ref "R30") (pin "P$1") (pinfunction "1_P$1") (pintype "passive"))
      (node (ref "U4") (pin "11") (pinfunction "P7_3_11") (pintype "bidirectional"))
    )
    (net (code "27") (name "ETH_RX_ER") (class "Default")
      (node (ref "R32") (pin "P$1") (pinfunction "1_P$1") (pintype "passive"))
      (node (ref "U4") (pin "12") (pinfunction "P7_4_12") (pintype "bidirectional"))
    )
    (net (code "28") (name "ETH_TXD0") (class "Default")
      (node (ref "U3") (pin "20") (pinfunction "TXD0_20") (pintype "input"))
      (node (ref "U4") (pin "8") (pinfunction "P7_0_8") (pintype "bidirectional"))
    )
    (net (code "29") (name "ETH_TXD1") (class "Default")
      (node (ref "U3") (pin "21") (pinfunction "TXD1_21") (pintype "bidirectional"))
      (node (ref "U4") (pin "7") (pinfunction "P4_6_7") (pintype "bidirectional"))
    )
    (net (code "30") (name "ETH_TXD_EN") (class "Default")
      (node (ref "U3") (pin "19") (pinfunction "TXEN_19") (pintype "input"))
      (node (ref "U4") (pin "6") (pinfunction "P4_5_6") (pintype "bidirectional"))
    )
    (net (code "31") (name "GND") (class "Default")
      (node (ref "C1") (pin "P$1") (pinfunction "1_P$1") (pintype "passive"))
      (node (ref "C10") (pin "P$1") (pinfunction "1_P$1") (pintype "passive"))
      (node (ref "C11") (pin "P$2") (pinfunction "2_P$2") (pintype "passive"))
      (node (ref "C13") (pin "P$1") (pinfunction "1_P$1") (pintype "passive"))
      (node (ref "C14") (pin "P$1") (pinfunction "1_P$1") (pintype "passive"))
      (node (ref "C15") (pin "2") (pinfunction "2_2") (pintype "passive"))
      (node (ref "C16") (pin "P$2") (pinfunction "2_P$2") (pintype "passive"))
      (node (ref "C17") (pin "P$1") (pinfunction "1_P$1") (pintype "passive"))
      (node (ref "C18") (pin "P$2") (pinfunction "2_P$2") (pintype "passive"))
      (node (ref "C19") (pin "P$2") (pinfunction "2_P$2") (pintype "passive"))
      (node (ref "C2") (pin "P$1") (pinfunction "1_P$1") (pintype "passive"))
      (node (ref "C20") (pin "P$2") (pinfunction "P$2_P$2") (pintype "bidirectional"))
      (node (ref "C21") (pin "P$2") (pinfunction "2_P$2") (pintype "passive"))
      (node (ref "C22") (pin "P$2") (pinfunction "2_P$2") (pintype "passive"))
      (node (ref "C23") (pin "2") (pinfunction "2_2") (pintype "passive"))
      (node (ref "C24") (pin "P$2") (pinfunction "2_P$2") (pintype "passive"))
      (node (ref "C25") (pin "P$2") (pinfunction "2_P$2") (pintype "passive"))
      (node (ref "C26") (pin "2") (pinfunction "2_2") (pintype "passive"))
      (node (ref "C27") (pin "P$2") (pinfunction "2_P$2") (pintype "passive"))
      (node (ref "C28") (pin "2") (pinfunction "2_2") (pintype "passive"))
      (node (ref "C29") (pin "P$2") (pinfunction "2_P$2") (pintype "passive"))
      (node (ref "C30") (pin "P$1") (pinfunction "1_P$1") (pintype "passive"))
      (node (ref "C31") (pin "P$2") (pinfunction "2_P$2") (pintype "passive"))
      (node (ref "C32") (pin "P$2") (pinfunction "2_P$2") (pintype "passive"))
      (node (ref "C34") (pin "P$1") (pinfunction "1_P$1") (pintype "passive"))
      (node (ref "C35") (pin "P$2") (pinfunction "2_P$2") (pintype "passive"))
      (node (ref "C36") (pin "P$1") (pinfunction "1_P$1") (pintype "passive"))
      (node (ref "C37") (pin "P$1") (pinfunction "1_P$1") (pintype "passive"))
      (node (ref "C38") (pin "P$2") (pinfunction "2_P$2") (pintype "passive"))
      (node (ref "C39") (pin "P$2") (pinfunction "2_P$2") (pintype "passive"))
      (node (ref "C40") (pin "P$2") (pinfunction "2_P$2") (pintype "passive"))
      (node (ref "C41") (pin "P$2") (pinfunction "2_P$2") (pintype "passive"))
      (node (ref "C42") (pin "P$2") (pinfunction "2_P$2") (pintype "passive"))
      (node (ref "C43") (pin "2") (pinfunction "2_2") (pintype "passive"))
      (node (ref "C44") (pin "P$2") (pinfunction "2_P$2") (pintype "passive"))
      (node (ref "C45") (pin "P$2") (pinfunction "2_P$2") (pintype "passive"))
      (node (ref "C46") (pin "P$2") (pinfunction "2_P$2") (pintype "passive"))
      (node (ref "C47") (pin "P$2") (pinfunction "2_P$2") (pintype "passive"))
      (node (ref "C48") (pin "2") (pinfunction "2_2") (pintype "passive"))
      (node (ref "C49") (pin "P$2") (pinfunction "2_P$2") (pintype "passive"))
      (node (ref "C5") (pin "P$2") (pinfunction "2_P$2") (pintype "passive"))
      (node (ref "C50") (pin "P$2") (pinfunction "2_P$2") (pintype "passive"))
      (node (ref "C51") (pin "P$2") (pinfunction "2_P$2") (pintype "passive"))
      (node (ref "C52") (pin "P$2") (pinfunction "2_P$2") (pintype "passive"))
      (node (ref "C53") (pin "P$2") (pinfunction "2_P$2") (pintype "passive"))
      (node (ref "C54") (pin "P$1") (pinfunction "1_P$1") (pintype "passive"))
      (node (ref "C55") (pin "P$1") (pinfunction "1_P$1") (pintype "passive"))
      (node (ref "C56") (pin "P$1") (pinfunction "1_P$1") (pintype "passive"))
      (node (ref "C57") (pin "P$2") (pinfunction "2_P$2") (pintype "passive"))
      (node (ref "C58") (pin "P$2") (pinfunction "2_P$2") (pintype "passive"))
      (node (ref "C59") (pin "P$2") (pinfunction "2_P$2") (pintype "passive"))
      (node (ref "C60") (pin "P$2") (pinfunction "2_P$2") (pintype "passive"))
      (node (ref "C61") (pin "P$1") (pinfunction "1_P$1") (pintype "passive"))
      (node (ref "C62") (pin "P$2") (pinfunction "2_P$2") (pintype "passive"))
      (node (ref "C63") (pin "P$2") (pinfunction "2_P$2") (pintype "passive"))
      (node (ref "C8") (pin "P$2") (pinfunction "2_P$2") (pintype "passive"))
      (node (ref "IC3") (pin "2") (pinfunction "GND_2") (pintype "power_in"))
      (node (ref "IC4") (pin "2") (pinfunction "GND_2") (pintype "power_in"))
      (node (ref "J1") (pin "P$19") (pinfunction "P$19_P$19") (pintype "bidirectional"))
      (node (ref "J11") (pin "10") (pinfunction "10_10") (pintype "passive"))
      (node (ref "J11") (pin "6") (pinfunction "6_6") (pintype "passive"))
      (node (ref "J11") (pin "8") (pinfunction "8_8") (pintype "passive"))
      (node (ref "J2") (pin "P$5") (pinfunction "GND_P$5") (pintype "bidirectional"))
      (node (ref "J3") (pin "GND") (pinfunction "GND_GND") (pintype "power_in"))
      (node (ref "J4") (pin "10") (pinfunction "GLO_10") (pintype "bidirectional"))
      (node (ref "J4") (pin "8") (pinfunction "P8_8") (pintype "bidirectional"))
      (node (ref "LED3") (pin "C") (pinfunction "C_C") (pintype "passive"))
      (node (ref "LED4") (pin "C") (pinfunction "C_C") (pintype "passive"))
      (node (ref "R14") (pin "P$1") (pinfunction "1_P$1") (pintype "passive"))
      (node (ref "R16") (pin "P$1") (pinfunction "1_P$1") (pintype "passive"))
      (node (ref "R17") (pin "P$1") (pinfunction "1_P$1") (pintype "passive"))
      (node (ref "R19") (pin "P$1") (pinfunction "1_P$1") (pintype "passive"))
      (node (ref "R21") (pin "P$1") (pinfunction "1_P$1") (pintype "passive"))
      (node (ref "R25") (pin "P$1") (pinfunction "1_P$1") (pintype "passive"))
      (node (ref "R7") (pin "P$1") (pinfunction "1_P$1") (pintype "passive"))
      (node (ref "U$1") (pin "P$14") (pinfunction "GND_P$14") (pintype "power_in"))
      (node (ref "U$1") (pin "P$20") (pinfunction "GND_P$20") (pintype "power_in"))
      (node (ref "U$1") (pin "P$25") (pinfunction "GND_P$25") (pintype "power_in"))
      (node (ref "U$1") (pin "P$30") (pinfunction "GND_P$30") (pintype "power_in"))
      (node (ref "U$1") (pin "P$34") (pinfunction "GND_P$34") (pintype "power_in"))
      (node (ref "U$1") (pin "P$39") (pinfunction "GND_P$39") (pintype "power_in"))
      (node (ref "U$1") (pin "P$6") (pinfunction "GND_P$6") (pintype "power_in"))
      (node (ref "U$1") (pin "P$9") (pinfunction "GND_P$9") (pintype "power_in"))
      (node (ref "U$2") (pin "P1") (pinfunction "GND_P1") (pintype "bidirectional"))
      (node (ref "U$2") (pin "P21") (pinfunction "GND1_P21") (pintype "bidirectional"))
      (node (ref "U$2") (pin "P23") (pinfunction "GND2_P23") (pintype "bidirectional"))
      (node (ref "U$3") (pin "2") (pinfunction "2_2") (pintype "bidirectional"))
      (node (ref "U$3") (pin "4") (pinfunction "4_4") (pintype "bidirectional"))
      (node (ref "U$4") (pin "P$2") (pinfunction "2_P$2") (pintype "passive"))
      (node (ref "U$7") (pin "P$2") (pinfunction "P$2_P$2") (pintype "bidirectional"))
      (node (ref "U$8") (pin "N-") (pinfunction "-_N-") (pintype "passive"))
      (node (ref "U2") (pin "2") (pinfunction "GND_2") (pintype "input"))
      (node (ref "U3") (pin "22") (pinfunction "GND_22") (pintype "power_in"))
      (node (ref "U3") (pin "25") (pinfunction "25_25") (pintype "passive"))
      (node (ref "U4") (pin "111") (pinfunction "VSS(IO)5_111") (pintype "bidirectional"))
      (node (ref "U4") (pin "124") (pinfunction "VSS(IO)6_124") (pintype "bidirectional"))
      (node (ref "U4") (pin "139") (pinfunction "VSS(IO)7_139") (pintype "bidirectional"))
      (node (ref "U4") (pin "150") (pinfunction "VSS(IO)8_150") (pintype "bidirectional"))
      (node (ref "U4") (pin "153") (pinfunction "VREFL_153") (pintype "bidirectional"))
      (node (ref "U4") (pin "156") (pinfunction "AVSS0_156") (pintype "bidirectional"))
      (node (ref "U4") (pin "157") (pinfunction "VREFL0_157") (pintype "bidirectional"))
      (node (ref "U4") (pin "170") (pinfunction "VSS(IO)9_170") (pintype "bidirectional"))
      (node (ref "U4") (pin "22") (pinfunction "VSS1_22") (pintype "bidirectional"))
      (node (ref "U4") (pin "28") (pinfunction "AVSS_USBHS_28") (pintype "bidirectional"))
      (node (ref "U4") (pin "29") (pinfunction "PVSS_USBHS_29") (pintype "bidirectional"))
      (node (ref "U4") (pin "30") (pinfunction "VSS2_USBHS_30") (pintype "bidirectional"))
      (node (ref "U4") (pin "33") (pinfunction "VSS1_USBHS_33") (pintype "bidirectional"))
      (node (ref "U4") (pin "35") (pinfunction "VSSIO_35") (pintype "bidirectional"))
      (node (ref "U4") (pin "45") (pinfunction "VSS_USB_45") (pintype "bidirectional"))
      (node (ref "U4") (pin "60") (pinfunction "VSS(IO)2_60") (pintype "bidirectional"))
      (node (ref "U4") (pin "63") (pinfunction "VSS(IO/DCDC)_63") (pintype "bidirectional"))
      (node (ref "U4") (pin "66") (pinfunction "VCC_DCDC(IO/DCDC)_66") (pintype "bidirectional"))
      (node (ref "U4") (pin "83") (pinfunction "VSS(IO)3_83") (pintype "bidirectional"))
      (node (ref "U4") (pin "98") (pinfunction "VSS(IO)4_98") (pintype "bidirectional"))
      (node (ref "U5") (pin "P$3") (pinfunction "VOUT-_P$3") (pintype "bidirectional"))
      (node (ref "U5") (pin "P$6") (pinfunction "AC_N_P$6") (pintype "bidirectional"))
      (node (ref "U6") (pin "2") (pinfunction "REF_2") (pintype "passive"))
      (node (ref "U6") (pin "3") (pinfunction "VS-_3") (pintype "power_in"))
      (node (ref "U7") (pin "2") (pinfunction "REF_2") (pintype "passive"))
      (node (ref "U7") (pin "3") (pinfunction "VS-_3") (pintype "power_in"))
      (node (ref "X4") (pin "2") (pinfunction "2_2") (pintype "bidirectional"))
      (node (ref "X4") (pin "4") (pinfunction "4_4") (pintype "bidirectional"))
    )
    (net (code "32") (name "GNDE") (class "Default")
      (node (ref "J2") (pin "P$6") (pinfunction "SHIELD1_P$6") (pintype "bidirectional"))
      (node (ref "J2") (pin "P$7") (pinfunction "SHIELD2_P$7") (pintype "bidirectional"))
      (node (ref "J2") (pin "P$8") (pinfunction "SHIELD3_P$8") (pintype "bidirectional"))
      (node (ref "J2") (pin "P$9") (pinfunction "SHIELD4_P$9") (pintype "bidirectional"))
      (node (ref "J3") (pin "SHLD1") (pinfunction "SHIELD_1_SHLD1") (pintype "bidirectional"))
      (node (ref "J3") (pin "SHLD2") (pinfunction "SHIELD_2_SHLD2") (pintype "bidirectional"))
      (node (ref "J4") (pin "13") (pinfunction "GNDE0_13") (pintype "bidirectional"))
      (node (ref "J4") (pin "14") (pinfunction "GNDE1_14") (pintype "bidirectional"))
    )
    (net (code "33") (name "GP4") (class "Default")
      (node (ref "U$1") (pin "P$7") (pinfunction "GP4_P$7") (pintype "bidirectional"))
      (node (ref "U4") (pin "49") (pinfunction "P2_7_49") (pintype "bidirectional"))
    )
    (net (code "34") (name "GP5") (class "Default")
      (node (ref "U$1") (pin "P$29") (pinfunction "GP5_P$29") (pintype "bidirectional"))
      (node (ref "U4") (pin "57") (pinfunction "P3_15_57") (pintype "bidirectional"))
    )
    (net (code "35") (name "GP6") (class "Default")
      (node (ref "U$1") (pin "P$31") (pinfunction "GP6_P$31") (pintype "bidirectional"))
      (node (ref "U4") (pin "59") (pinfunction "P9_1_59") (pintype "bidirectional"))
    )
    (net (code "36") (name "GP12") (class "Default")
      (node (ref "U$1") (pin "P$32") (pinfunction "GP12_P$32") (pintype "bidirectional"))
      (node (ref "U4") (pin "58") (pinfunction "P9_0_58") (pintype "bidirectional"))
    )
    (net (code "37") (name "GP13") (class "Default")
      (node (ref "U$1") (pin "P$33") (pinfunction "GP13_P$33") (pintype "bidirectional"))
      (node (ref "U4") (pin "76") (pinfunction "P3_10_76") (pintype "bidirectional"))
    )
    (net (code "38") (name "GP14") (class "Default")
      (node (ref "U$1") (pin "P$8") (pinfunction "TXO_P$8") (pintype "output"))
      (node (ref "U4") (pin "42") (pinfunction "P4_9_42") (pintype "bidirectional"))
    )
    (net (code "39") (name "GP15") (class "Default")
      (node (ref "U$1") (pin "P$10") (pinfunction "RXI_P$10") (pintype "input"))
      (node (ref "U4") (pin "43") (pinfunction "P4_8_43") (pintype "bidirectional"))
    )
    (net (code "40") (name "GP16") (class "Default")
      (node (ref "U$1") (pin "P$36") (pinfunction "GP16_P$36") (pintype "bidirectional"))
      (node (ref "U4") (pin "79") (pinfunction "P3_7_79") (pintype "bidirectional"))
    )
    (net (code "41") (name "GP17") (class "Default")
      (node (ref "U$1") (pin "P$11") (pinfunction "GP17_P$11") (pintype "bidirectional"))
      (node (ref "U4") (pin "51") (pinfunction "P2_5_51") (pintype "bidirectional"))
    )
    (net (code "42") (name "GP18") (class "Default")
      (node (ref "U$1") (pin "P$12") (pinfunction "GP18#_P$12") (pintype "bidirectional"))
      (node (ref "U4") (pin "50") (pinfunction "P2_6_50") (pintype "bidirectional"))
    )
    (net (code "43") (name "GP19") (class "Default")
      (node (ref "U$1") (pin "P$35") (pinfunction "GP19_P$35") (pintype "bidirectional"))
      (node (ref "U4") (pin "77") (pinfunction "P3_9_77") (pintype "bidirectional"))
    )
    (net (code "44") (name "GP20") (class "Default")
      (node (ref "U$1") (pin "P$38") (pinfunction "GP20_P$38") (pintype "bidirectional"))
      (node (ref "U4") (pin "81") (pinfunction "P3_5_81") (pintype "bidirectional"))
    )
    (net (code "45") (name "GP21") (class "Default")
      (node (ref "U$1") (pin "P$40") (pinfunction "GP21_P$40") (pintype "bidirectional"))
      (node (ref "U4") (pin "82") (pinfunction "P3_4_82") (pintype "bidirectional"))
    )
    (net (code "46") (name "GP22") (class "Default")
      (node (ref "U$1") (pin "P$15") (pinfunction "GP22_P$15") (pintype "bidirectional"))
      (node (ref "U4") (pin "72") (pinfunction "P9_6_72") (pintype "bidirectional"))
    )
    (net (code "47") (name "GP23") (class "Default")
      (node (ref "U$1") (pin "P$16") (pinfunction "GP23_P$16") (pintype "bidirectional"))
      (node (ref "U4") (pin "71") (pinfunction "P9_7_71") (pintype "bidirectional"))
    )
    (net (code "48") (name "GP24") (class "Default")
      (node (ref "U$1") (pin "P$18") (pinfunction "GP24_P$18") (pintype "bidirectional"))
      (node (ref "U4") (pin "73") (pinfunction "P9_5_73") (pintype "bidirectional"))
    )
    (net (code "49") (name "GP25") (class "Default")
      (node (ref "U$1") (pin "P$22") (pinfunction "GP25_P$22") (pintype "bidirectional"))
      (node (ref "U4") (pin "56") (pinfunction "P3_14_56") (pintype "bidirectional"))
    )
    (net (code "50") (name "GP26") (class "Default")
      (node (ref "U$1") (pin "P$37") (pinfunction "GP26_P$37") (pintype "bidirectional"))
      (node (ref "U4") (pin "80") (pinfunction "P3_6_80") (pintype "bidirectional"))
    )
    (net (code "51") (name "GP27") (class "Default")
      (node (ref "U$1") (pin "P$13") (pinfunction "GP27_P$13") (pintype "bidirectional"))
      (node (ref "U4") (pin "70") (pinfunction "P9_8_70") (pintype "bidirectional"))
    )
    (net (code "52") (name "ID") (class "Default")
      (node (ref "J2") (pin "P$4") (pinfunction "ID_P$4") (pintype "bidirectional"))
    )
    (net (code "53") (name "ID_SC") (class "Default")
      (node (ref "U$1") (pin "P$28") (pinfunction "ID_SC_P$28") (pintype "bidirectional"))
      (node (ref "U4") (pin "93") (pinfunction "P1_12_93") (pintype "bidirectional"))
    )
    (net (code "54") (name "ID_SD") (class "Default")
      (node (ref "U$1") (pin "P$27") (pinfunction "ID_SD_P$27") (pintype "bidirectional"))
      (node (ref "U4") (pin "92") (pinfunction "P1_11_92") (pintype "bidirectional"))
    )
    (net (code "55") (name "IIC_0_SCL") (class "Default")
      (node (ref "U$1") (pin "P$5") (pinfunction "SCL_P$5") (pintype "bidirectional"))
      (node (ref "U4") (pin "1") (pinfunction "P4_0_1") (pintype "bidirectional"))
    )
    (net (code "56") (name "IIC_0_SDA") (class "Default")
      (node (ref "U$1") (pin "P$3") (pinfunction "SDA_P$3") (pintype "bidirectional"))
      (node (ref "U4") (pin "2") (pinfunction "P4_1_2") (pintype "bidirectional"))
    )
    (net (code "57") (name "IRQ0") (class "Default")
      (node (ref "U$2") (pin "P10") (pinfunction "IRQ0_P10") (pintype "bidirectional"))
      (node (ref "U4") (pin "86") (pinfunction "P3_2_86") (pintype "bidirectional"))
    )
    (net (code "58") (name "IRQ1") (class "Default")
      (node (ref "U$2") (pin "P11") (pinfunction "IRQ1_P11") (pintype "bidirectional"))
      (node (ref "U4") (pin "87") (pinfunction "P3_1_87") (pintype "bidirectional"))
    )
    (net (code "59") (name "LED1{slash}SPEED") (class "Default")
      (node (ref "J4") (pin "11") (pinfunction "YLO_11") (pintype "bidirectional"))
      (node (ref "U3") (pin "23") (pinfunction "LED0/ANEN_SPEED_23") (pintype "bidirectional"))
    )
    (net (code "60") (name "M0_STEP") (class "Default")
      (node (ref "U4") (pin "16") (pinfunction "PB_0_16") (pintype "bidirectional"))
    )
    (net (code "61") (name "NC") (class "Default")
      (node (ref "J4") (pin "7") (pinfunction "P7_7") (pintype "bidirectional"))
    )
    (net (code "62") (name "Net-(C16-1)") (class "Default")
      (node (ref "C16") (pin "P$1") (pinfunction "1_P$1") (pintype "passive"))
      (node (ref "J2") (pin "P$1") (pinfunction "VBUS_P$1") (pintype "bidirectional"))
      (node (ref "R4") (pin "P$2") (pinfunction "2_P$2") (pintype "passive"))
      (node (ref "R7") (pin "P$2") (pinfunction "2_P$2") (pintype "passive"))
    )
    (net (code "63") (name "Net-(C31-1)") (class "Default")
      (node (ref "C31") (pin "P$1") (pinfunction "1_P$1") (pintype "passive"))
      (node (ref "U4") (pin "62") (pinfunction "VCL1_62") (pintype "bidirectional"))
    )
    (net (code "64") (name "Net-(C37-2)") (class "Default")
      (node (ref "C37") (pin "P$2") (pinfunction "2_P$2") (pintype "passive"))
      (node (ref "U4") (pin "148") (pinfunction "VCL2_148") (pintype "bidirectional"))
    )
    (net (code "65") (name "Net-(C38-1)") (class "Default")
      (node (ref "C38") (pin "P$1") (pinfunction "1_P$1") (pintype "passive"))
      (node (ref "U4") (pin "19") (pinfunction "VCLO_19") (pintype "bidirectional"))
    )
    (net (code "66") (name "Net-(C44-1)") (class "Default")
      (node (ref "C43") (pin "1") (pinfunction "1_1") (pintype "passive"))
      (node (ref "C44") (pin "P$1") (pinfunction "1_P$1") (pintype "passive"))
      (node (ref "FB2/2") (pin "2") (pinfunction "P$2_2") (pintype "bidirectional"))
      (node (ref "U3") (pin "2") (pinfunction "VDDA_3.3_2") (pintype "power_in"))
    )
    (net (code "67") (name "Net-(J2-D+)") (class "Default")
      (node (ref "J2") (pin "P$3") (pinfunction "D+_P$3") (pintype "bidirectional"))
      (node (ref "R6") (pin "P$2") (pinfunction "2_P$2") (pintype "passive"))
    )
    (net (code "68") (name "Net-(J2-D-)") (class "Default")
      (node (ref "J2") (pin "P$2") (pinfunction "D-_P$2") (pintype "bidirectional"))
      (node (ref "R5") (pin "P$2") (pinfunction "2_P$2") (pintype "passive"))
    )
    (net (code "69") (name "Net-(R8-2)") (class "Default")
      (node (ref "LED3") (pin "A") (pinfunction "A_A") (pintype "passive"))
      (node (ref "R8") (pin "P$2") (pinfunction "2_P$2") (pintype "passive"))
    )
    (net (code "70") (name "Net-(R9-2)") (class "Default")
      (node (ref "LED4") (pin "A") (pinfunction "A_A") (pintype "passive"))
      (node (ref "R9") (pin "P$2") (pinfunction "2_P$2") (pintype "passive"))
    )
    (net (code "71") (name "Net-(R16-2)") (class "Default")
      (node (ref "R16") (pin "P$2") (pinfunction "2_P$2") (pintype "passive"))
      (node (ref "U4") (pin "65") (pinfunction "VLO2(DCDC)_65") (pintype "bidirectional"))
    )
    (net (code "72") (name "Net-(R17-2)") (class "Default")
      (node (ref "R17") (pin "P$2") (pinfunction "2_P$2") (pintype "passive"))
      (node (ref "U4") (pin "64") (pinfunction "VLO1(DCDC)_64") (pintype "bidirectional"))
    )
    (net (code "73") (name "Net-(R19-2)") (class "Default")
      (node (ref "R19") (pin "P$2") (pinfunction "2_P$2") (pintype "passive"))
      (node (ref "U4") (pin "27") (pinfunction "USBHS_RREF_27") (pintype "bidirectional"))
    )
    (net (code "74") (name "P0_02") (class "Default")
      (node (ref "J1") (pin "P$6") (pinfunction "P$6_P$6") (pintype "bidirectional"))
      (node (ref "U4") (pin "167") (pinfunction "P0_2/AN002_167") (pintype "bidirectional"))
    )
    (net (code "75") (name "P0_03") (class "Default")
      (node (ref "J1") (pin "P$5") (pinfunction "P$5_P$5") (pintype "bidirectional"))
      (node (ref "U4") (pin "166") (pinfunction "P0_3/PGAVSS000_166") (pintype "bidirectional"))
    )
    (net (code "76") (name "P0_04") (class "Default")
      (node (ref "J1") (pin "P$8") (pinfunction "P$8_P$8") (pintype "bidirectional"))
      (node (ref "U4") (pin "165") (pinfunction "P0_4/AN100_165") (pintype "bidirectional"))
    )
    (net (code "77") (name "P0_07") (class "Default")
      (node (ref "J1") (pin "P$7") (pinfunction "P$7_P$7") (pintype "bidirectional"))
      (node (ref "U4") (pin "162") (pinfunction "P0_7/PGVSS100_162") (pintype "bidirectional"))
    )
    (net (code "78") (name "P0_14") (class "Default")
      (node (ref "J1") (pin "P$10") (pinfunction "P$10_P$10") (pintype "bidirectional"))
      (node (ref "U4") (pin "152") (pinfunction "P0_14/DA0/AN005/AN105_152") (pintype "bidirectional"))
    )
    (net (code "79") (name "P0_15") (class "Default")
      (node (ref "J1") (pin "P$9") (pinfunction "P$9_P$9") (pintype "bidirectional"))
      (node (ref "U4") (pin "151") (pinfunction "P0_15/DA1/AN006/AN106_151") (pintype "bidirectional"))
    )
    (net (code "80") (name "P1_05") (class "Default")
      (node (ref "U4") (pin "127") (pinfunction "P1_5_127") (pintype "bidirectional"))
    )
    (net (code "81") (name "P1_13") (class "Default")
      (node (ref "U4") (pin "94") (pinfunction "P1_13_94") (pintype "bidirectional"))
    )
    (net (code "82") (name "P1_14") (class "Default")
      (node (ref "U4") (pin "95") (pinfunction "P1_14_95") (pintype "bidirectional"))
    )
    (net (code "83") (name "P1_15") (class "Default")
      (node (ref "U4") (pin "96") (pinfunction "P1_15_96") (pintype "bidirectional"))
    )
    (net (code "84") (name "P2_00") (class "Default")
      (node (ref "U4") (pin "69") (pinfunction "P2_0(INPUT_ONLY)_69") (pintype "bidirectional"))
    )
    (net (code "85") (name "P2_01") (class "Default")
      (node (ref "U4") (pin "68") (pinfunction "P2_1/MD_68") (pintype "bidirectional"))
    )
    (net (code "86") (name "P3_03") (class "Default")
      (node (ref "U4") (pin "85") (pinfunction "P3_3_85") (pintype "bidirectional"))
    )
    (net (code "87") (name "P3_11") (class "Default")
      (node (ref "U4") (pin "75") (pinfunction "P3_11_75") (pintype "bidirectional"))
    )
    (net (code "88") (name "P4_02") (class "Default")
      (node (ref "U4") (pin "3") (pinfunction "P4_2_3") (pintype "bidirectional"))
    )
    (net (code "89") (name "P4_10") (class "Default")
      (node (ref "U4") (pin "41") (pinfunction "P4_10_41") (pintype "bidirectional"))
    )
    (net (code "90") (name "P4_11") (class "Default")
      (node (ref "U4") (pin "40") (pinfunction "P4_11_40") (pintype "bidirectional"))
    )
    (net (code "91") (name "P4_12") (class "Default")
      (node (ref "U4") (pin "39") (pinfunction "P4_12_39") (pintype "bidirectional"))
    )
    (net (code "92") (name "P4_13") (class "Default")
      (node (ref "U4") (pin "38") (pinfunction "P4_13_38") (pintype "bidirectional"))
    )
    (net (code "93") (name "P4_14") (class "Default")
      (node (ref "U4") (pin "37") (pinfunction "P4_14_37") (pintype "bidirectional"))
    )
    (net (code "94") (name "P4_15") (class "Default")
      (node (ref "U4") (pin "36") (pinfunction "P4_15_36") (pintype "bidirectional"))
    )
    (net (code "95") (name "P5_00") (class "Default")
      (node (ref "J1") (pin "P$17") (pinfunction "P$17_P$17") (pintype "bidirectional"))
      (node (ref "U4") (pin "140") (pinfunction "P5_0/AN016_140") (pintype "bidirectional"))
    )
    (net (code "96") (name "P5_01") (class "Default")
      (node (ref "J1") (pin "P$18") (pinfunction "P$18_P$18") (pintype "bidirectional"))
      (node (ref "U4") (pin "141") (pinfunction "P5_1/AN116_141") (pintype "bidirectional"))
    )
    (net (code "97") (name "P5_02") (class "Default")
      (node (ref "J1") (pin "P$15") (pinfunction "P$15_P$15") (pintype "bidirectional"))
      (node (ref "U4") (pin "142") (pinfunction "P5_2/AN017_142") (pintype "bidirectional"))
    )
    (net (code "98") (name "P5_03") (class "Default")
      (node (ref "J1") (pin "P$16") (pinfunction "P$16_P$16") (pintype "bidirectional"))
      (node (ref "U4") (pin "143") (pinfunction "P5_3/AN117_143") (pintype "bidirectional"))
    )
    (net (code "99") (name "P5_04") (class "Default")
      (node (ref "J1") (pin "P$13") (pinfunction "P$13_P$13") (pintype "bidirectional"))
      (node (ref "U4") (pin "144") (pinfunction "P5_4/AN018_144") (pintype "bidirectional"))
    )
    (net (code "100") (name "P5_05") (class "Default")
      (node (ref "J1") (pin "P$14") (pinfunction "P$14_P$14") (pintype "bidirectional"))
      (node (ref "U4") (pin "145") (pinfunction "P5_5/AN118_145") (pintype "bidirectional"))
    )
    (net (code "101") (name "P5_06") (class "Default")
      (node (ref "J1") (pin "P$11") (pinfunction "P$11_P$11") (pintype "bidirectional"))
      (node (ref "U4") (pin "146") (pinfunction "P5_6/AN019_146") (pintype "bidirectional"))
    )
    (net (code "102") (name "P5_07") (class "Default")
      (node (ref "J1") (pin "P$12") (pinfunction "P$12_P$12") (pintype "bidirectional"))
      (node (ref "U4") (pin "147") (pinfunction "P5_7/AN119_147") (pintype "bidirectional"))
    )
    (net (code "103") (name "P5_11") (class "Default")
      (node (ref "J1") (pin "P$2") (pinfunction "P$2_P$2") (pintype "bidirectional"))
      (node (ref "U4") (pin "176") (pinfunction "P5_11_176") (pintype "bidirectional"))
    )
    (net (code "104") (name "P5_12") (class "Default")
      (node (ref "J1") (pin "P$1") (pinfunction "P$1_P$1") (pintype "bidirectional"))
      (node (ref "U4") (pin "175") (pinfunction "P5_12_175") (pintype "bidirectional"))
    )
    (net (code "105") (name "P5_13") (class "Default")
      (node (ref "J1") (pin "P$4") (pinfunction "P$4_P$4") (pintype "bidirectional"))
      (node (ref "U4") (pin "174") (pinfunction "P5_13_174") (pintype "bidirectional"))
    )
    (net (code "106") (name "P6_02") (class "Default")
      (node (ref "U4") (pin "120") (pinfunction "P6_2_120") (pintype "bidirectional"))
    )
    (net (code "107") (name "P6_03") (class "Default")
      (node (ref "U4") (pin "119") (pinfunction "P6_3_119") (pintype "bidirectional"))
    )
    (net (code "108") (name "P6_04") (class "Default")
      (node (ref "U4") (pin "118") (pinfunction "P6_4_118") (pintype "bidirectional"))
    )
    (net (code "109") (name "P6_05") (class "Default")
      (node (ref "U4") (pin "117") (pinfunction "P6_5_117") (pintype "bidirectional"))
    )
    (net (code "110") (name "P6_06") (class "Default")
      (node (ref "U4") (pin "116") (pinfunction "P6_6_116") (pintype "bidirectional"))
    )
    (net (code "111") (name "P6_07") (class "Default")
      (node (ref "U4") (pin "115") (pinfunction "P6_7_115") (pintype "bidirectional"))
    )
    (net (code "112") (name "P6_08") (class "Default")
      (node (ref "U4") (pin "99") (pinfunction "P6_8_99") (pintype "bidirectional"))
    )
    (net (code "113") (name "P6_09") (class "Default")
      (node (ref "U4") (pin "100") (pinfunction "P6_9_100") (pintype "bidirectional"))
    )
    (net (code "114") (name "P6_10") (class "Default")
      (node (ref "U4") (pin "101") (pinfunction "P6_10_101") (pintype "bidirectional"))
    )
    (net (code "115") (name "P6_11") (class "Default")
      (node (ref "U4") (pin "102") (pinfunction "P6_11_102") (pintype "bidirectional"))
    )
    (net (code "116") (name "P6_12") (class "Default")
      (node (ref "U4") (pin "103") (pinfunction "P6_12_103") (pintype "bidirectional"))
    )
    (net (code "117") (name "P6_13") (class "Default")
      (node (ref "U4") (pin "104") (pinfunction "P6_13_104") (pintype "bidirectional"))
    )
    (net (code "118") (name "P6_14") (class "Default")
      (node (ref "U4") (pin "105") (pinfunction "P6_14_105") (pintype "bidirectional"))
    )
    (net (code "119") (name "P6_15") (class "Default")
      (node (ref "U4") (pin "106") (pinfunction "P6_15_106") (pintype "bidirectional"))
    )
    (net (code "120") (name "P7_06") (class "Default")
      (node (ref "U4") (pin "14") (pinfunction "P7_6_14") (pintype "bidirectional"))
    )
    (net (code "121") (name "P7_07") (class "Default")
      (node (ref "U4") (pin "15") (pinfunction "P7_7_15") (pintype "bidirectional"))
    )
    (net (code "122") (name "P8_03") (class "Default")
      (node (ref "U4") (pin "136") (pinfunction "P8_3_136") (pintype "bidirectional"))
    )
    (net (code "123") (name "P8_04") (class "Default")
      (node (ref "U4") (pin "137") (pinfunction "P8_4_137") (pintype "bidirectional"))
    )
    (net (code "124") (name "P8_05") (class "Default")
      (node (ref "J1") (pin "P$3") (pinfunction "P$3_P$3") (pintype "bidirectional"))
      (node (ref "U4") (pin "173") (pinfunction "P8_5_173") (pintype "bidirectional"))
    )
    (net (code "125") (name "PA_00") (class "Default")
      (node (ref "U4") (pin "114") (pinfunction "PA_0_114") (pintype "bidirectional"))
    )
    (net (code "126") (name "PA_01") (class "Default")
      (node (ref "U4") (pin "113") (pinfunction "PA_1_113") (pintype "bidirectional"))
    )
    (net (code "127") (name "PA_08") (class "Default")
      (node (ref "U4") (pin "107") (pinfunction "PA_8_107") (pintype "bidirectional"))
    )
    (net (code "128") (name "PA_09") (class "Default")
      (node (ref "U4") (pin "108") (pinfunction "PA_9_108") (pintype "bidirectional"))
    )
    (net (code "129") (name "PA_10") (class "Default")
      (node (ref "U4") (pin "109") (pinfunction "PA_10_109") (pintype "bidirectional"))
    )
    (net (code "130") (name "PM0") (class "Default")
      (node (ref "U$2") (pin "P12") (pinfunction "PM0_P12") (pintype "bidirectional"))
      (node (ref "U4") (pin "126") (pinfunction "P1_6_126") (pintype "bidirectional"))
    )
    (net (code "131") (name "PM1") (class "Default")
      (node (ref "U$2") (pin "P13") (pinfunction "PM1_P13") (pintype "bidirectional"))
      (node (ref "U4") (pin "125") (pinfunction "P1_7_125") (pintype "bidirectional"))
    )
    (net (code "132") (name "R51") (class "Default")
      (node (ref "J4") (pin "12") (pinfunction "YHI_12") (pintype "bidirectional"))
      (node (ref "R23") (pin "P$1") (pinfunction "1_P$1") (pintype "passive"))
    )
    (net (code "133") (name "R52") (class "Default")
      (node (ref "J4") (pin "9") (pinfunction "GHI_9") (pintype "bidirectional"))
      (node (ref "R24") (pin "P$1") (pinfunction "1_P$1") (pintype "passive"))
    )
    (net (code "134") (name "RESET") (class "Default")
      (node (ref "C57") (pin "P$1") (pinfunction "1_P$1") (pintype "passive"))
      (node (ref "J11") (pin "9") (pinfunction "9_9") (pintype "passive"))
      (node (ref "R18") (pin "P$1") (pinfunction "1_P$1") (pintype "passive"))
      (node (ref "U4") (pin "67") (pinfunction "RES#_67") (pintype "bidirectional"))
    )
    (net (code "135") (name "REXT") (class "Default")
      (node (ref "C47") (pin "P$1") (pinfunction "1_P$1") (pintype "passive"))
      (node (ref "R25") (pin "P$2") (pinfunction "2_P$2") (pintype "passive"))
      (node (ref "U3") (pin "9") (pinfunction "REXT_9") (pintype "input"))
    )
    (net (code "136") (name "RST") (class "Default")
      (node (ref "U$2") (pin "P20") (pinfunction "RST_P20") (pintype "bidirectional"))
      (node (ref "U4") (pin "121") (pinfunction "P6_1_121") (pintype "bidirectional"))
    )
    (net (code "137") (name "RXD0") (class "Default")
      (node (ref "R31") (pin "P$2") (pinfunction "2_P$2") (pintype "passive"))
      (node (ref "U3") (pin "13") (pinfunction "RXD0_13") (pintype "bidirectional"))
    )
    (net (code "138") (name "RXD1") (class "Default")
      (node (ref "R30") (pin "P$2") (pinfunction "2_P$2") (pintype "passive"))
      (node (ref "U3") (pin "12") (pinfunction "RXD1_12") (pintype "bidirectional"))
    )
    (net (code "139") (name "RXER") (class "Default")
      (node (ref "R32") (pin "P$2") (pinfunction "2_P$2") (pintype "passive"))
      (node (ref "U3") (pin "17") (pinfunction "RXER_17") (pintype "bidirectional"))
    )
    (net (code "140") (name "RXM") (class "Default")
      (node (ref "J4") (pin "6") (pinfunction "RD-_6") (pintype "bidirectional"))
      (node (ref "U3") (pin "3") (pinfunction "RXM_3") (pintype "bidirectional"))
    )
    (net (code "141") (name "RXP") (class "Default")
      (node (ref "J4") (pin "3") (pinfunction "RD+_3") (pintype "bidirectional"))
      (node (ref "U3") (pin "4") (pinfunction "RXP_4") (pintype "bidirectional"))
    )
    (net (code "142") (name "SPI_0_CS_0") (class "Default")
      (node (ref "U$2") (pin "P16") (pinfunction "CS_P16") (pintype "bidirectional"))
      (node (ref "U4") (pin "129") (pinfunction "P1_3_129") (pintype "bidirectional"))
    )
    (net (code "143") (name "SPI_0_MISO") (class "Default")
      (node (ref "U$2") (pin "P18") (pinfunction "SDO_P18") (pintype "bidirectional"))
      (node (ref "U4") (pin "132") (pinfunction "P1_0_132") (pintype "bidirectional"))
    )
    (net (code "144") (name "SPI_0_MOSI") (class "Default")
      (node (ref "U$2") (pin "P15") (pinfunction "SDI_P15") (pintype "bidirectional"))
      (node (ref "U4") (pin "131") (pinfunction "P1_1_131") (pintype "bidirectional"))
    )
    (net (code "145") (name "SPI_0_SCLK") (class "Default")
      (node (ref "U$2") (pin "P17") (pinfunction "SCLK_P17") (pintype "bidirectional"))
      (node (ref "U4") (pin "130") (pinfunction "P1_2_130") (pintype "bidirectional"))
    )
    (net (code "146") (name "SPI_1_CS_0") (class "Default")
      (node (ref "U$1") (pin "P$24") (pinfunction "CE0_P$24") (pintype "output"))
      (node (ref "U4") (pin "55") (pinfunction "P3_13_55") (pintype "bidirectional"))
    )
    (net (code "147") (name "SPI_1_CS_1") (class "Default")
      (node (ref "U$1") (pin "P$26") (pinfunction "CE1_P$26") (pintype "output"))
      (node (ref "U4") (pin "74") (pinfunction "P3_12_74") (pintype "bidirectional"))
    )
    (net (code "148") (name "SPI_1_MISO") (class "Default")
      (node (ref "U$1") (pin "P$21") (pinfunction "MISO_P$21") (pintype "input"))
      (node (ref "U4") (pin "54") (pinfunction "P2_2_54") (pintype "bidirectional"))
    )
    (net (code "149") (name "SPI_1_MOSI") (class "Default")
      (node (ref "U$1") (pin "P$19") (pinfunction "MOSI_P$19") (pintype "output"))
      (node (ref "U4") (pin "53") (pinfunction "P2_3_53") (pintype "bidirectional"))
    )
    (net (code "150") (name "SPI_1_SCLK") (class "Default")
      (node (ref "U$1") (pin "P$23") (pinfunction "SCLK_P$23") (pintype "output"))
      (node (ref "U4") (pin "52") (pinfunction "P2_4_52") (pintype "bidirectional"))
    )
    (net (code "151") (name "TCK") (class "Default")
      (node (ref "J11") (pin "7") (pinfunction "7_7") (pintype "passive"))
      (node (ref "U4") (pin "88") (pinfunction "P3_0_88") (pintype "bidirectional"))
    )
    (net (code "152") (name "TDI") (class "Default")
      (node (ref "J11") (pin "1") (pinfunction "1_1") (pintype "passive"))
      (node (ref "U4") (pin "91") (pinfunction "P1_10_91") (pintype "bidirectional"))
    )
    (net (code "153") (name "TDO") (class "Default")
      (node (ref "J11") (pin "3") (pinfunction "3_3") (pintype "passive"))
      (node (ref "U4") (pin "90") (pinfunction "P1_9_90") (pintype "bidirectional"))
    )
    (net (code "154") (name "TMS") (class "Default")
      (node (ref "J11") (pin "5") (pinfunction "5_5") (pintype "passive"))
      (node (ref "U4") (pin "89") (pinfunction "P1_8_89") (pintype "bidirectional"))
    )
    (net (code "155") (name "TXM") (class "Default")
      (node (ref "J4") (pin "2") (pinfunction "TD-_2") (pintype "bidirectional"))
      (node (ref "U3") (pin "5") (pinfunction "TXM_5") (pintype "bidirectional"))
    )
    (net (code "156") (name "TXP") (class "Default")
      (node (ref "J4") (pin "1") (pinfunction "TD+_1") (pintype "bidirectional"))
      (node (ref "U3") (pin "6") (pinfunction "TXP_6") (pintype "bidirectional"))
    )
    (net (code "157") (name "UC") (class "Default")
      (node (ref "C20") (pin "P$1") (pinfunction "P$1_P$1") (pintype "bidirectional"))
      (node (ref "U$2") (pin "P22") (pinfunction "VAC_240_P22") (pintype "bidirectional"))
      (node (ref "U$7") (pin "P$1") (pinfunction "P$1_P$1") (pintype "bidirectional"))
      (node (ref "U5") (pin "P$5") (pinfunction "AC_L_P$5") (pintype "bidirectional"))
    )
    (net (code "158") (name "USBHS_FAULT") (class "Default")
      (node (ref "R12") (pin "P$1") (pinfunction "1_P$1") (pintype "passive"))
      (node (ref "U2") (pin "3") (pinfunction "FLG_3") (pintype "input"))
      (node (ref "U4") (pin "78") (pinfunction "P3_8_78") (pintype "bidirectional"))
    )
    (net (code "159") (name "USBHS_N") (class "Default")
      (node (ref "J3") (pin "D-") (pinfunction "D-_D-") (pintype "bidirectional"))
      (node (ref "U4") (pin "31") (pinfunction "USBHS_DM_31") (pintype "bidirectional"))
    )
    (net (code "160") (name "USBHS_P") (class "Default")
      (node (ref "J3") (pin "D+") (pinfunction "D+_D+") (pintype "bidirectional"))
      (node (ref "U4") (pin "32") (pinfunction "USBHS_DP_32") (pintype "bidirectional"))
    )
    (net (code "161") (name "USBHS_VBUS") (class "Default")
      (node (ref "C11") (pin "P$1") (pinfunction "1_P$1") (pintype "passive"))
      (node (ref "C15") (pin "1") (pinfunction "1_1") (pintype "passive"))
      (node (ref "J3") (pin "VBUS") (pinfunction "VBUS_VBUS") (pintype "power_in"))
      (node (ref "U2") (pin "5") (pinfunction "OUT_5") (pintype "input"))
      (node (ref "U4") (pin "17") (pinfunction "PB_1_17") (pintype "bidirectional"))
    )
    (net (code "162") (name "USBHS_VBUSEN") (class "Default")
      (node (ref "R1") (pin "P$1") (pinfunction "1_P$1") (pintype "passive"))
      (node (ref "U2") (pin "1") (pinfunction "EN_1") (pintype "input"))
    )
    (net (code "163") (name "USB_N") (class "Default")
      (node (ref "R5") (pin "P$1") (pinfunction "1_P$1") (pintype "passive"))
      (node (ref "U4") (pin "46") (pinfunction "USB_DM_46") (pintype "bidirectional"))
    )
    (net (code "164") (name "USB_P") (class "Default")
      (node (ref "R6") (pin "P$1") (pinfunction "1_P$1") (pintype "passive"))
      (node (ref "U4") (pin "47") (pinfunction "USB_DP_47") (pintype "bidirectional"))
    )
    (net (code "165") (name "USB_VBUS_B") (class "Default")
      (node (ref "R4") (pin "P$1") (pinfunction "1_P$1") (pintype "passive"))
      (node (ref "U4") (pin "44") (pinfunction "P4_7_44") (pintype "bidirectional"))
    )
    (net (code "166") (name "VCC") (class "Default")
      (node (ref "C21") (pin "P$1") (pinfunction "1_P$1") (pintype "passive"))
      (node (ref "C22") (pin "P$1") (pinfunction "1_P$1") (pintype "passive"))
      (node (ref "C23") (pin "1") (pinfunction "1_1") (pintype "passive"))
      (node (ref "C24") (pin "P$1") (pinfunction "1_P$1") (pintype "passive"))
      (node (ref "IC3") (pin "1") (pinfunction "IN_1") (pintype "input"))
      (node (ref "IC4") (pin "1") (pinfunction "IN_1") (pintype "input"))
      (node (ref "U$8") (pin "P+") (pinfunction "+_P+") (pintype "passive"))
      (node (ref "U5") (pin "P$2") (pinfunction "VOUT+_P$2") (pintype "bidirectional"))
    )
    (net (code "167") (name "VCL_F(FLASH)") (class "Default")
      (node (ref "C36") (pin "P$2") (pinfunction "2_P$2") (pintype "passive"))
      (node (ref "U4") (pin "112") (pinfunction "VCL_F(FLASH)_112") (pintype "bidirectional"))
    )
    (net (code "168") (name "VDD") (class "Default")
      (node (ref "C1") (pin "P$2") (pinfunction "2_P$2") (pintype "passive"))
      (node (ref "C10") (pin "P$2") (pinfunction "2_P$2") (pintype "passive"))
      (node (ref "C13") (pin "P$2") (pinfunction "2_P$2") (pintype "passive"))
      (node (ref "C14") (pin "P$2") (pinfunction "2_P$2") (pintype "passive"))
      (node (ref "C19") (pin "P$1") (pinfunction "1_P$1") (pintype "passive"))
      (node (ref "C2") (pin "P$2") (pinfunction "2_P$2") (pintype "passive"))
      (node (ref "C25") (pin "P$1") (pinfunction "1_P$1") (pintype "passive"))
      (node (ref "C26") (pin "1") (pinfunction "1_1") (pintype "passive"))
      (node (ref "C29") (pin "P$1") (pinfunction "1_P$1") (pintype "passive"))
      (node (ref "C30") (pin "P$2") (pinfunction "2_P$2") (pintype "passive"))
      (node (ref "C32") (pin "P$1") (pinfunction "1_P$1") (pintype "passive"))
      (node (ref "C48") (pin "1") (pinfunction "1_1") (pintype "passive"))
      (node (ref "C49") (pin "P$1") (pinfunction "1_P$1") (pintype "passive"))
      (node (ref "C54") (pin "P$2") (pinfunction "2_P$2") (pintype "passive"))
      (node (ref "C55") (pin "P$2") (pinfunction "2_P$2") (pintype "passive"))
      (node (ref "C56") (pin "P$2") (pinfunction "2_P$2") (pintype "passive"))
      (node (ref "C58") (pin "P$1") (pinfunction "1_P$1") (pintype "passive"))
      (node (ref "C59") (pin "P$1") (pinfunction "1_P$1") (pintype "passive"))
      (node (ref "C60") (pin "P$1") (pinfunction "1_P$1") (pintype "passive"))
      (node (ref "C61") (pin "P$2") (pinfunction "2_P$2") (pintype "passive"))
      (node (ref "C62") (pin "P$1") (pinfunction "1_P$1") (pintype "passive"))
      (node (ref "C63") (pin "P$1") (pinfunction "1_P$1") (pintype "passive"))
      (node (ref "FB2/2") (pin "1") (pinfunction "P$1_1") (pintype "bidirectional"))
      (node (ref "IC4") (pin "3") (pinfunction "OUT_3") (pintype "output"))
      (node (ref "J1") (pin "P$20") (pinfunction "P$20_P$20") (pintype "bidirectional"))
      (node (ref "J11") (pin "2") (pinfunction "2_2") (pintype "passive"))
      (node (ref "J11") (pin "4") (pinfunction "4_4") (pintype "passive"))
      (node (ref "R18") (pin "P$2") (pinfunction "2_P$2") (pintype "passive"))
      (node (ref "R23") (pin "P$2") (pinfunction "2_P$2") (pintype "passive"))
      (node (ref "R24") (pin "P$2") (pinfunction "2_P$2") (pintype "passive"))
      (node (ref "R26") (pin "P$2") (pinfunction "2_P$2") (pintype "passive"))
      (node (ref "R27") (pin "P$2") (pinfunction "2_P$2") (pintype "passive"))
      (node (ref "R28") (pin "P$2") (pinfunction "2_P$2") (pintype "passive"))
      (node (ref "R29") (pin "P$2") (pinfunction "2_P$2") (pintype "passive"))
      (node (ref "R8") (pin "P$1") (pinfunction "1_P$1") (pintype "passive"))
      (node (ref "U$1") (pin "P$1") (pinfunction "3.3V_P$1") (pintype "power_in"))
      (node (ref "U$1") (pin "P$17") (pinfunction "3.3V_P$17") (pintype "power_in"))
      (node (ref "U$2") (pin "P19") (pinfunction "VDD_P19") (pintype "bidirectional"))
      (node (ref "U3") (pin "14") (pinfunction "VDDIO_14") (pintype "power_in"))
      (node (ref "U4") (pin "110") (pinfunction "VCC(IO)5_110") (pintype "bidirectional"))
      (node (ref "U4") (pin "123") (pinfunction "VCC(IO)6_123") (pintype "bidirectional"))
      (node (ref "U4") (pin "138") (pinfunction "VCC(IO)7_138") (pintype "bidirectional"))
      (node (ref "U4") (pin "149") (pinfunction "VCC(IO)8_149") (pintype "bidirectional"))
      (node (ref "U4") (pin "154") (pinfunction "VREFH_154") (pintype "bidirectional"))
      (node (ref "U4") (pin "155") (pinfunction "AVCC0_155") (pintype "bidirectional"))
      (node (ref "U4") (pin "158") (pinfunction "VREFH0_158") (pintype "bidirectional"))
      (node (ref "U4") (pin "171") (pinfunction "VCC(IO)9_171") (pintype "bidirectional"))
      (node (ref "U4") (pin "25") (pinfunction "VCC1_25") (pintype "bidirectional"))
      (node (ref "U4") (pin "26") (pinfunction "AVCC_SUBHS_26") (pintype "bidirectional"))
      (node (ref "U4") (pin "34") (pinfunction "VCC_USBHS_34") (pintype "bidirectional"))
      (node (ref "U4") (pin "48") (pinfunction "VCC_USB_48") (pintype "bidirectional"))
      (node (ref "U4") (pin "61") (pinfunction "VCC(IO)2_61") (pintype "bidirectional"))
      (node (ref "U4") (pin "84") (pinfunction "VCC(IO)3_84") (pintype "bidirectional"))
      (node (ref "U4") (pin "97") (pinfunction "VCC(IO)4_97") (pintype "bidirectional"))
      (node (ref "U6") (pin "7") (pinfunction "+VS_7") (pintype "power_in"))
      (node (ref "U7") (pin "7") (pinfunction "+VS_7") (pintype "power_in"))
    )
    (net (code "169") (name "VDD5") (class "Default")
      (node (ref "C27") (pin "P$1") (pinfunction "1_P$1") (pintype "passive"))
      (node (ref "C28") (pin "1") (pinfunction "1_1") (pintype "passive"))
      (node (ref "C5") (pin "P$1") (pinfunction "1_P$1") (pintype "passive"))
      (node (ref "C8") (pin "P$1") (pinfunction "1_P$1") (pintype "passive"))
      (node (ref "IC3") (pin "3") (pinfunction "OUT_3") (pintype "output"))
      (node (ref "R1") (pin "P$2") (pinfunction "2_P$2") (pintype "passive"))
      (node (ref "R12") (pin "P$2") (pinfunction "2_P$2") (pintype "passive"))
      (node (ref "R9") (pin "P$1") (pinfunction "1_P$1") (pintype "passive"))
      (node (ref "U$1") (pin "P$2") (pinfunction "5V_P$2") (pintype "power_in"))
      (node (ref "U$1") (pin "P$4") (pinfunction "5V_P$4") (pintype "power_in"))
      (node (ref "U2") (pin "4") (pinfunction "VIN_4") (pintype "input"))
    )
    (net (code "170") (name "VDD_1.2") (class "Default")
      (node (ref "C45") (pin "P$1") (pinfunction "1_P$1") (pintype "passive"))
      (node (ref "C46") (pin "P$1") (pinfunction "1_P$1") (pintype "passive"))
      (node (ref "U3") (pin "1") (pinfunction "VDD_1.2_1") (pintype "power_in"))
    )
    (net (code "171") (name "WARNOUT") (class "Default")
      (node (ref "U$2") (pin "P9") (pinfunction "WARNOUT_P9") (pintype "bidirectional"))
      (node (ref "U4") (pin "128") (pinfunction "P1_4_128") (pintype "bidirectional"))
    )
    (net (code "172") (name "XCIN") (class "Default")
      (node (ref "C50") (pin "P$1") (pinfunction "1_P$1") (pintype "passive"))
      (node (ref "U4") (pin "20") (pinfunction "XCIN_20") (pintype "bidirectional"))
      (node (ref "X3") (pin "P$1") (pinfunction "P$1_P$1") (pintype "bidirectional"))
    )
    (net (code "173") (name "XCOUT") (class "Default")
      (node (ref "C51") (pin "P$1") (pinfunction "1_P$1") (pintype "passive"))
      (node (ref "U4") (pin "21") (pinfunction "XCOUT_21") (pintype "bidirectional"))
      (node (ref "X3") (pin "P$2") (pinfunction "P$2_P$2") (pintype "bidirectional"))
    )
    (net (code "174") (name "XII") (class "Default")
      (node (ref "C42") (pin "P$1") (pinfunction "1_P$1") (pintype "passive"))
      (node (ref "U$3") (pin "1") (pinfunction "1_1") (pintype "bidirectional"))
      (node (ref "U3") (pin "8") (pinfunction "XI_8") (pintype "input"))
    )
    (net (code "175") (name "XOO") (class "Default")
      (node (ref "C41") (pin "P$1") (pinfunction "1_P$1") (pintype "passive"))
      (node (ref "U$3") (pin "3") (pinfunction "3_3") (pintype "bidirectional"))
      (node (ref "U3") (pin "7") (pinfunction "XO_7") (pintype "output"))
    )
    (net (code "176") (name "XTAL1") (class "Default")
      (node (ref "C52") (pin "P$1") (pinfunction "1_P$1") (pintype "passive"))
      (node (ref "U4") (pin "23") (pinfunction "P2_13/XTAL_23") (pintype "bidirectional"))
      (node (ref "X4") (pin "1") (pinfunction "1_1") (pintype "bidirectional"))
    )
    (net (code "177") (name "XTAL2") (class "Default")
      (node (ref "C53") (pin "P$1") (pinfunction "1_P$1") (pintype "passive"))
      (node (ref "U4") (pin "24") (pinfunction "P2_12/EXTAL_24") (pintype "bidirectional"))
      (node (ref "X4") (pin "3") (pinfunction "3_3") (pintype "bidirectional"))
    )
    (net (code "178") (name "ZX0") (class "Default")
      (node (ref "U$2") (pin "P2") (pinfunction "ZX0_P2") (pintype "bidirectional"))
      (node (ref "U4") (pin "135") (pinfunction "P8_2_135") (pintype "bidirectional"))
    )
    (net (code "179") (name "ZX1") (class "Default")
      (node (ref "U$2") (pin "P3") (pinfunction "ZX1_P3") (pintype "bidirectional"))
      (node (ref "U4") (pin "134") (pinfunction "P8_1_134") (pintype "bidirectional"))
    )
    (net (code "180") (name "ZX2") (class "Default")
      (node (ref "U$2") (pin "P4") (pinfunction "ZX2_P4") (pintype "bidirectional"))
      (node (ref "U4") (pin "133") (pinfunction "P8_0_133") (pintype "bidirectional"))
    )
    (net (code "181") (name "unconnected-(U4-VBAT-Pad18)") (class "Default")
      (node (ref "U4") (pin "18") (pinfunction "VBAT_18") (pintype "bidirectional"))
    )
    (net (code "182") (name "unconnected-(U5-NC1-PadP$1)") (class "Default")
      (node (ref "U5") (pin "P$1") (pinfunction "NC1_P$1") (pintype "bidirectional"))
    )
    (net (code "183") (name "unconnected-(U5-NC2-PadP$4)") (class "Default")
      (node (ref "U5") (pin "P$4") (pinfunction "NC2_P$4") (pintype "bidirectional"))
    )
    (net (code "184") (name "unconnected-(U5-NC3-PadP$7)") (class "Default")
      (node (ref "U5") (pin "P$7") (pinfunction "NC3_P$7") (pintype "bidirectional"))
    )
    (net (code "185") (name "unconnected-(U6-NC-Pad4)") (class "Default")
      (node (ref "U6") (pin "4") (pinfunction "NC_4") (pintype "no_connect"))
    )
    (net (code "186") (name "unconnected-(U7-NC-Pad4)") (class "Default")
      (node (ref "U7") (pin "4") (pinfunction "NC_4") (pintype "no_connect"))
    )
  )
)
